# AutoPBT.net
KiCad netlist of a schematic drawn in EAGLE
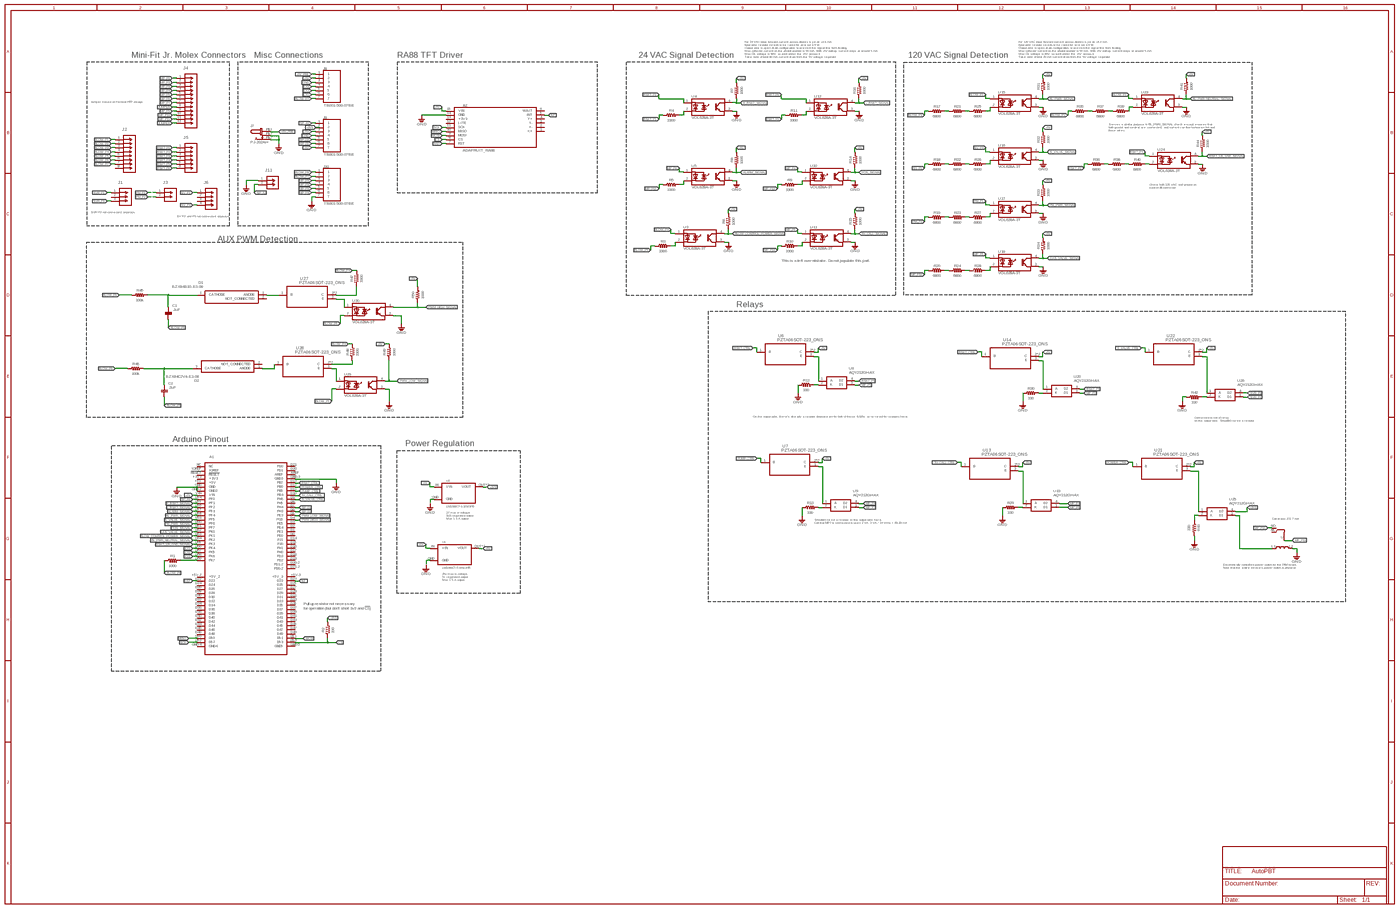
[diagram p0: schematic, sheet 1, overview]
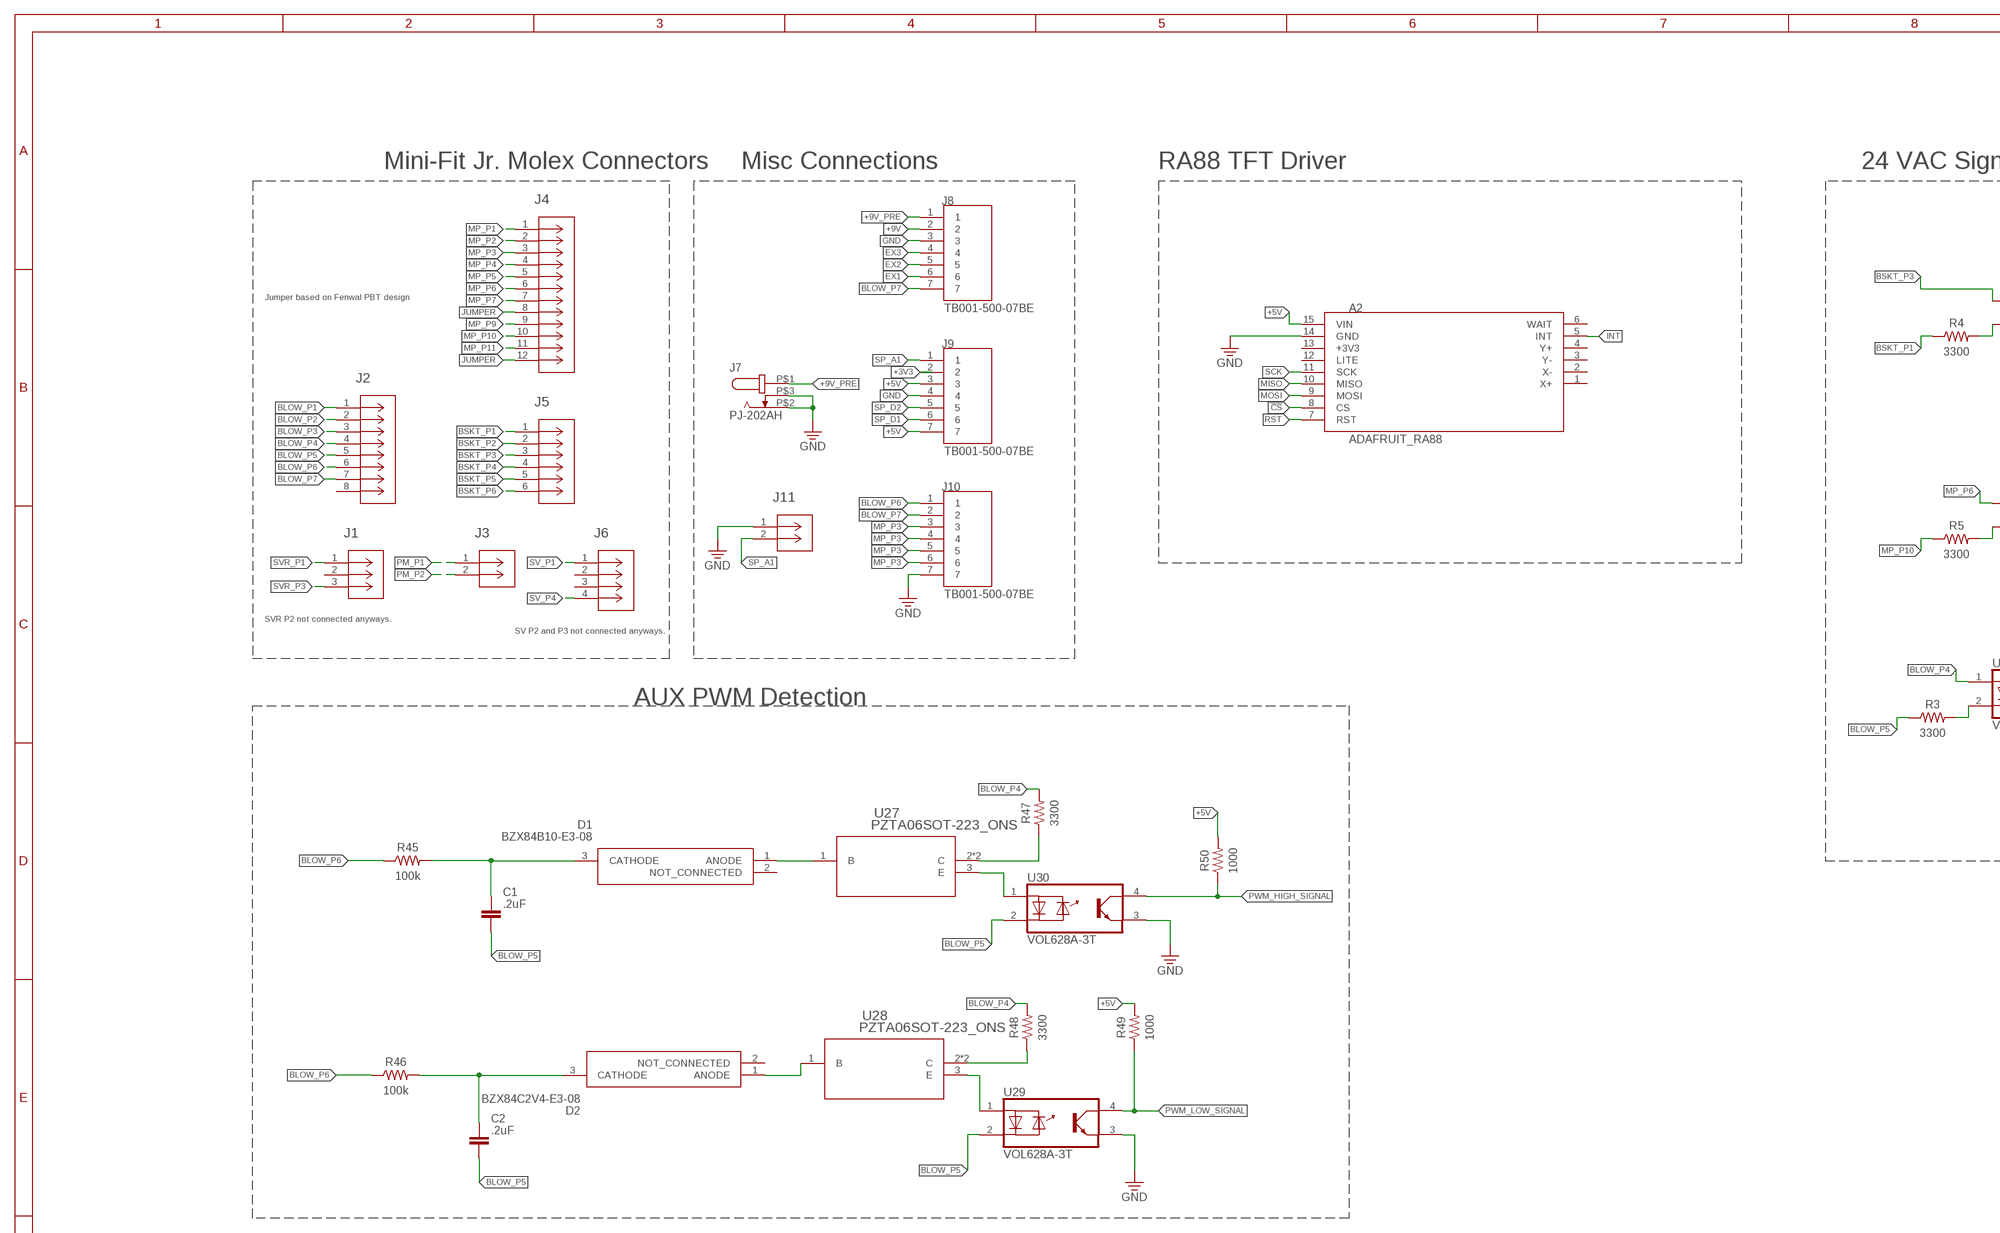
[diagram p1: schematic, sheet 1, part 1 of 4]
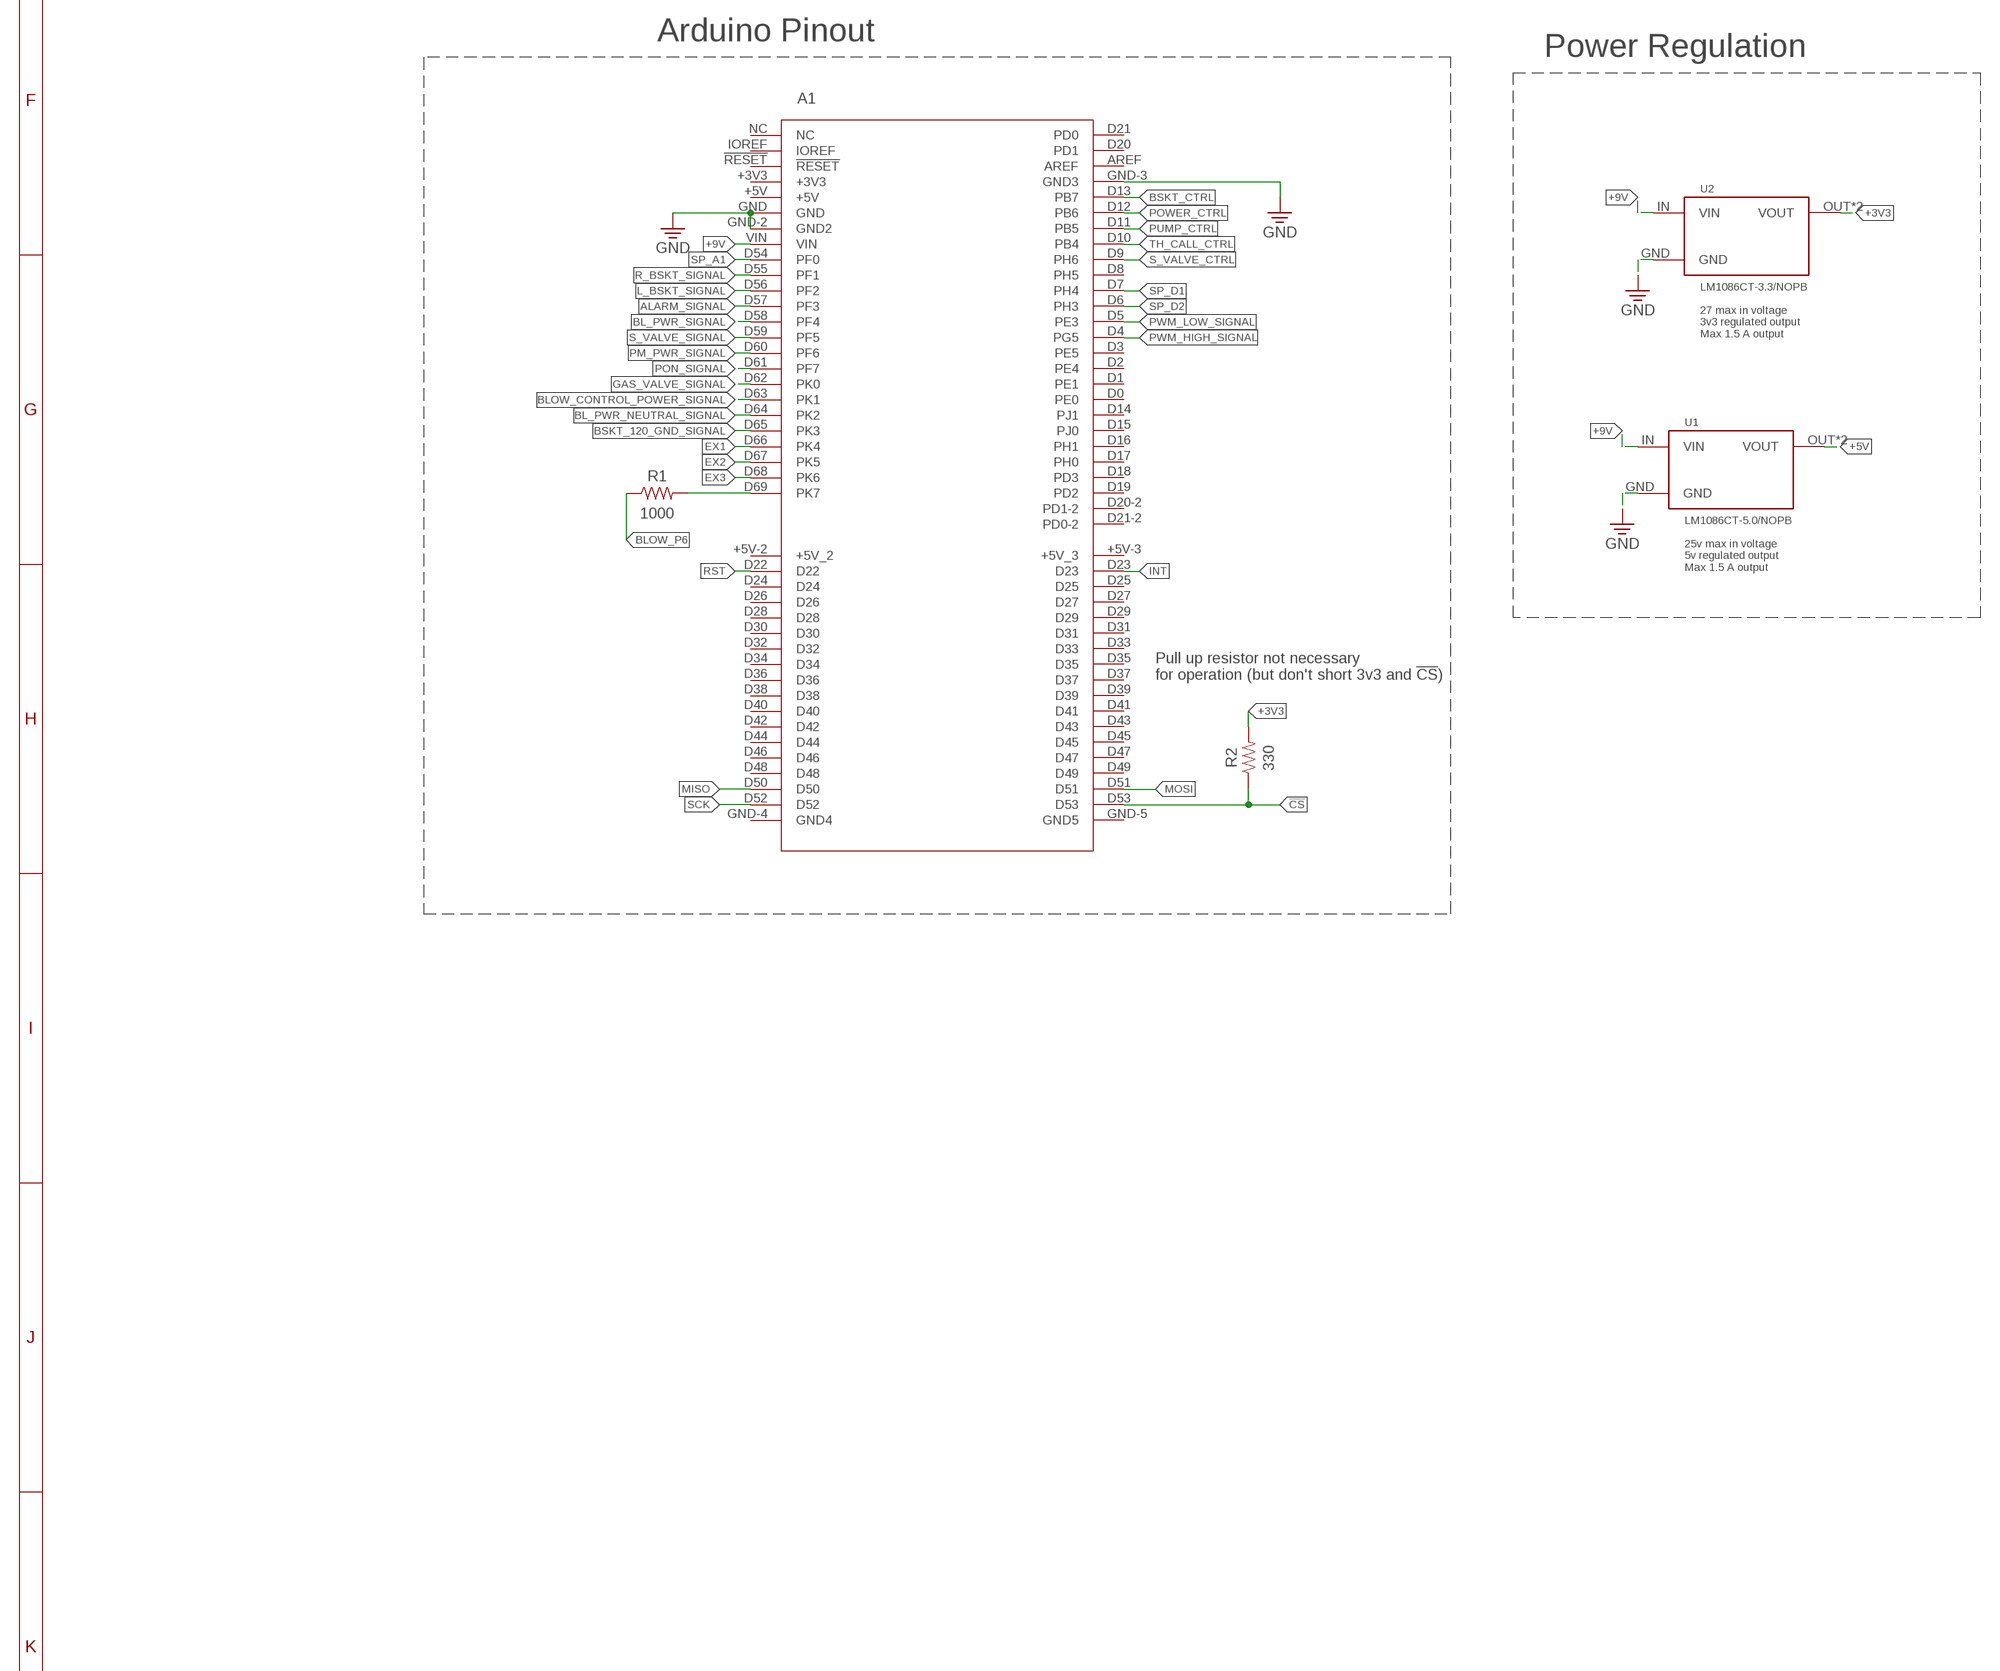
[diagram p2: schematic, sheet 1, part 2 of 4]
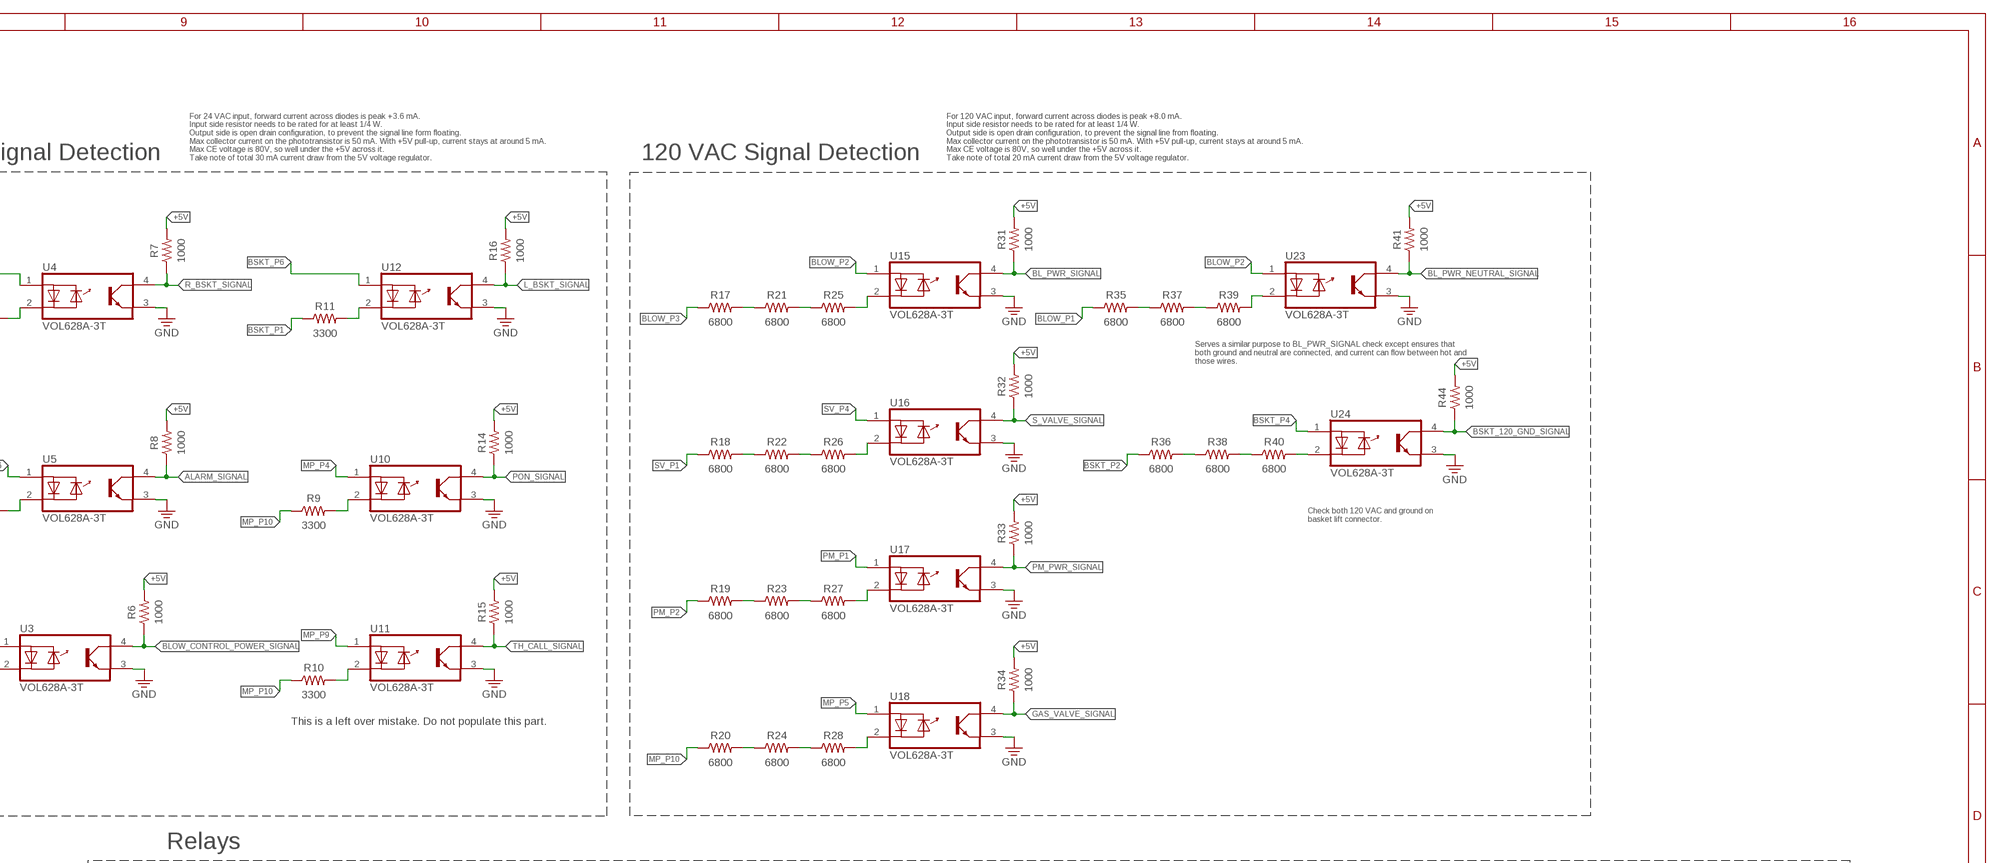
[diagram p3: schematic, sheet 1, part 3 of 4]
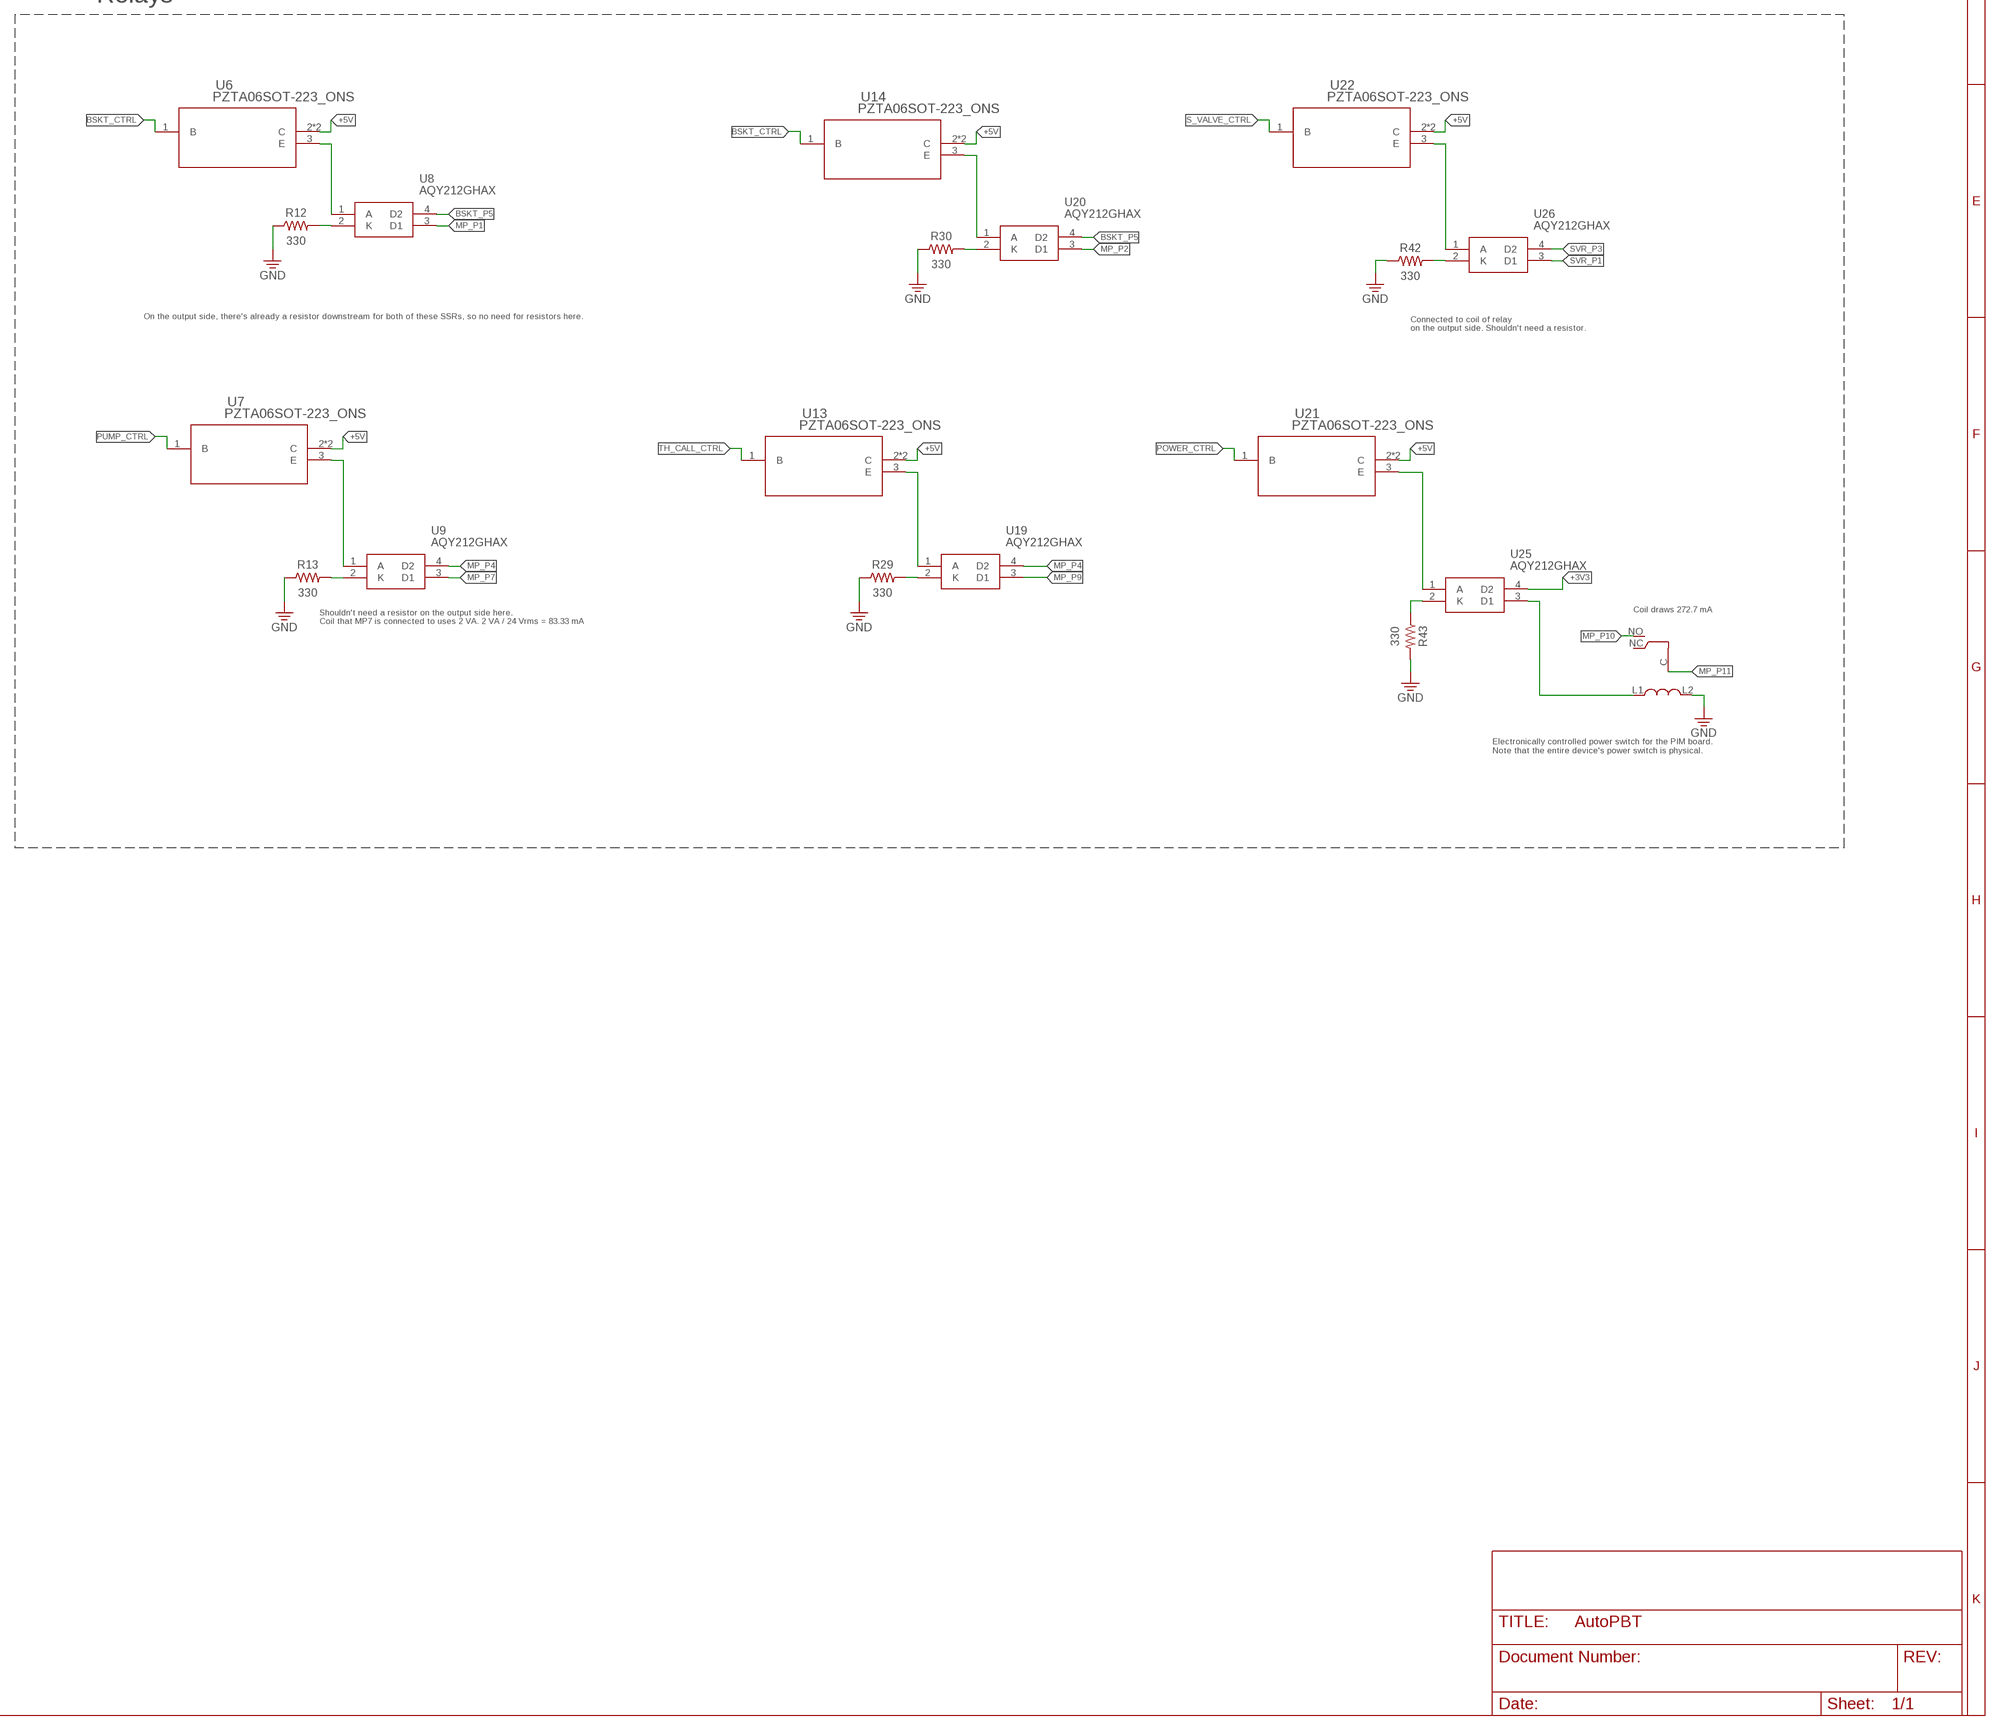
[diagram p4: schematic, sheet 1, part 4 of 4]

(export (version "E")
  (design (tool "Eeschema 10.0.6"))
  (components
    (comp (ref "A1")
      (value "ARDUINO2560ARDUINO2560ACTUAL")
      (footprint "eagle-import:ARDUINO2560PINS")
      (libsource (lib "eagle-import") (part "ARDUINO2560ARDUINO2560ACTUAL"))
    )
    (comp (ref "A2")
      (value "ADAFRUIT_RA88")
      (footprint "eagle-import:RA88")
      (libsource (lib "eagle-import") (part "ADAFRUIT_RA88"))
    )
    (comp (ref "C1")
      (value ".2uF")
      (footprint "eagle-import:CAPC3216X135")
      (libsource (lib "eagle-import") (part "CCHIP-1206(3216-METRIC)_"))
    )
    (comp (ref "C2")
      (value ".2uF")
      (footprint "eagle-import:CAPC3216X135")
      (libsource (lib "eagle-import") (part "CCHIP-1206(3216-METRIC)_"))
    )
    (comp (ref "D1")
      (value "BZX84B10-E3-08")
      (footprint "eagle-import:SOT95P248X115-3N")
      (libsource (lib "eagle-import") (part "BZX84B10-E3-08"))
    )
    (comp (ref "D2")
      (value "BZX84C2V4-E3-08")
      (footprint "eagle-import:SOT95P248X115-3N")
      (fields (field (name "MOUSER_PART_NUMBER") "78-BZX84C2V4-E3-08"))
      (libsource (lib "eagle-import") (part "BZX84C2V4-E3-08"))
    )
    (comp (ref "J1")
      (value "39301039CON_39301039")
      (footprint "eagle-import:CON_39301039")
      (fields
        (field (name "MANUFACTURER_PART_NUMBER") "39301039")
        (field (name "COPYRIGHT") "Copyright (C) 2022 Ultra Librarian. All rights reserved.")
      )
      (libsource (lib "eagle-import") (part "39301039CON_39301039"))
    )
    (comp (ref "J2")
      (value "39281083CON_39281083")
      (footprint "eagle-import:CON_39281083")
      (fields
        (field (name "MANUFACTURER_PART_NUMBER") "39281083")
        (field (name "COPYRIGHT") "Copyright (C) 2022 Ultra Librarian. All rights reserved.")
      )
      (libsource (lib "eagle-import") (part "39281083CON_39281083"))
    )
    (comp (ref "J3")
      (value "39281023CON_39281023")
      (footprint "eagle-import:CON_39281023")
      (fields
        (field (name "MANUFACTURER_PART_NUMBER") "39281023")
        (field (name "COPYRIGHT") "Copyright (C) 2022 Ultra Librarian. All rights reserved.")
      )
      (libsource (lib "eagle-import") (part "39281023CON_39281023"))
    )
    (comp (ref "J4")
      (value "39281123CON_39281123")
      (footprint "eagle-import:CON_39281123")
      (fields
        (field (name "MANUFACTURER_PART_NUMBER") "39281123")
        (field (name "COPYRIGHT") "Copyright (C) 2022 Ultra Librarian. All rights reserved.")
      )
      (libsource (lib "eagle-import") (part "39281123CON_39281123"))
    )
    (comp (ref "J5")
      (value "39281063CON_39281063")
      (footprint "eagle-import:CON_39281063")
      (fields
        (field (name "MANUFACTURER_PART_NUMBER") "39281063")
        (field (name "COPYRIGHT") "Copyright (C) 2022 Ultra Librarian. All rights reserved.")
      )
      (libsource (lib "eagle-import") (part "39281063CON_39281063"))
    )
    (comp (ref "J6")
      (value "39299046CON_39299046")
      (footprint "eagle-import:CON_39299046")
      (fields
        (field (name "MANUFACTURER_PART_NUMBER") "39299046")
        (field (name "COPYRIGHT") "Copyright (C) 2022 Ultra Librarian. All rights reserved.")
      )
      (libsource (lib "eagle-import") (part "39299046CON_39299046"))
    )
    (comp (ref "J7")
      (value "PJ-202AH")
      (footprint "eagle-import:CUI_PJ-202AH")
      (fields (field (name "MANUFACTURER") "CUI INC"))
      (libsource (lib "eagle-import") (part "PJ-202AH"))
    )
    (comp (ref "J8")
      (value "TB001-500-07BE")
      (footprint "eagle-import:CUI_TB001-500-07BE")
      (fields (field (name "MANUFACTURER") "CUI"))
      (libsource (lib "eagle-import") (part "TB001-500-07BE"))
    )
    (comp (ref "J9")
      (value "TB001-500-07BE")
      (footprint "eagle-import:CUI_TB001-500-07BE")
      (fields (field (name "MANUFACTURER") "CUI"))
      (libsource (lib "eagle-import") (part "TB001-500-07BE"))
    )
    (comp (ref "J10")
      (value "TB001-500-07BE")
      (footprint "eagle-import:CUI_TB001-500-07BE")
      (fields (field (name "MANUFACTURER") "CUI"))
      (libsource (lib "eagle-import") (part "TB001-500-07BE"))
    )
    (comp (ref "J11")
      (value "430450212CON_430450212_MOL")
      (footprint "eagle-import:CON_430450212_MOL")
      (fields
        (field (name "MANUFACTURER_PART_NUMBER") "430450212")
        (field (name "COPYRIGHT") "Copyright (C) 2022 Ultra Librarian. All rights reserved.")
      )
      (libsource (lib "eagle-import") (part "430450212CON_430450212_MOL"))
    )
    (comp (ref "K1")
      (value "J107F1CS203VDC.80")
      (footprint "eagle-import:J107F1CS203VDC.80")
      (libsource (lib "eagle-import") (part "J107F1CS203VDC.80"))
    )
    (comp (ref "R1")
      (value "1000")
      (footprint "eagle-import:RESC1608X60")
      (libsource (lib "eagle-import") (part "R-USCHIP-0603(1608-METRIC)_"))
    )
    (comp (ref "R2")
      (value "330")
      (footprint "eagle-import:RESC1608X60")
      (libsource (lib "eagle-import") (part "R-USCHIP-0603(1608-METRIC)_"))
    )
    (comp (ref "R3")
      (value "3300")
      (footprint "eagle-import:RESC1608X60")
      (libsource (lib "eagle-import") (part "R-USCHIP-0603(1608-METRIC)_"))
    )
    (comp (ref "R4")
      (value "3300")
      (footprint "eagle-import:RESC1608X60")
      (libsource (lib "eagle-import") (part "R-USCHIP-0603(1608-METRIC)_"))
    )
    (comp (ref "R5")
      (value "3300")
      (footprint "eagle-import:RESC1608X60")
      (libsource (lib "eagle-import") (part "R-USCHIP-0603(1608-METRIC)_"))
    )
    (comp (ref "R6")
      (value "1000")
      (footprint "eagle-import:RESC1608X60")
      (libsource (lib "eagle-import") (part "R-USCHIP-0603(1608-METRIC)_"))
    )
    (comp (ref "R7")
      (value "1000")
      (footprint "eagle-import:RESC1608X60")
      (libsource (lib "eagle-import") (part "R-USCHIP-0603(1608-METRIC)_"))
    )
    (comp (ref "R8")
      (value "1000")
      (footprint "eagle-import:RESC1608X60")
      (libsource (lib "eagle-import") (part "R-USCHIP-0603(1608-METRIC)_"))
    )
    (comp (ref "R9")
      (value "3300")
      (footprint "eagle-import:RESC1608X60")
      (libsource (lib "eagle-import") (part "R-USCHIP-0603(1608-METRIC)_"))
    )
    (comp (ref "R10")
      (value "3300")
      (footprint "eagle-import:RESC1608X60")
      (libsource (lib "eagle-import") (part "R-USCHIP-0603(1608-METRIC)_"))
    )
    (comp (ref "R11")
      (value "3300")
      (footprint "eagle-import:RESC1608X60")
      (libsource (lib "eagle-import") (part "R-USCHIP-0603(1608-METRIC)_"))
    )
    (comp (ref "R12")
      (value "330")
      (footprint "eagle-import:RESC1608X60")
      (libsource (lib "eagle-import") (part "R-USCHIP-0603(1608-METRIC)_"))
    )
    (comp (ref "R13")
      (value "330")
      (footprint "eagle-import:RESC1608X60")
      (libsource (lib "eagle-import") (part "R-USCHIP-0603(1608-METRIC)_"))
    )
    (comp (ref "R14")
      (value "1000")
      (footprint "eagle-import:RESC1608X60")
      (libsource (lib "eagle-import") (part "R-USCHIP-0603(1608-METRIC)_"))
    )
    (comp (ref "R15")
      (value "1000")
      (footprint "eagle-import:RESC1608X60")
      (libsource (lib "eagle-import") (part "R-USCHIP-0603(1608-METRIC)_"))
    )
    (comp (ref "R16")
      (value "1000")
      (footprint "eagle-import:RESC1608X60")
      (libsource (lib "eagle-import") (part "R-USCHIP-0603(1608-METRIC)_"))
    )
    (comp (ref "R17")
      (value "6800")
      (footprint "eagle-import:RESC1608X60")
      (libsource (lib "eagle-import") (part "R-USCHIP-0603(1608-METRIC)_"))
    )
    (comp (ref "R18")
      (value "6800")
      (footprint "eagle-import:RESC1608X60")
      (libsource (lib "eagle-import") (part "R-USCHIP-0603(1608-METRIC)_"))
    )
    (comp (ref "R19")
      (value "6800")
      (footprint "eagle-import:RESC1608X60")
      (libsource (lib "eagle-import") (part "R-USCHIP-0603(1608-METRIC)_"))
    )
    (comp (ref "R20")
      (value "6800")
      (footprint "eagle-import:RESC1608X60")
      (libsource (lib "eagle-import") (part "R-USCHIP-0603(1608-METRIC)_"))
    )
    (comp (ref "R21")
      (value "6800")
      (footprint "eagle-import:RESC1608X60")
      (libsource (lib "eagle-import") (part "R-USCHIP-0603(1608-METRIC)_"))
    )
    (comp (ref "R22")
      (value "6800")
      (footprint "eagle-import:RESC1608X60")
      (libsource (lib "eagle-import") (part "R-USCHIP-0603(1608-METRIC)_"))
    )
    (comp (ref "R23")
      (value "6800")
      (footprint "eagle-import:RESC1608X60")
      (libsource (lib "eagle-import") (part "R-USCHIP-0603(1608-METRIC)_"))
    )
    (comp (ref "R24")
      (value "6800")
      (footprint "eagle-import:RESC1608X60")
      (libsource (lib "eagle-import") (part "R-USCHIP-0603(1608-METRIC)_"))
    )
    (comp (ref "R25")
      (value "6800")
      (footprint "eagle-import:RESC1608X60")
      (libsource (lib "eagle-import") (part "R-USCHIP-0603(1608-METRIC)_"))
    )
    (comp (ref "R26")
      (value "6800")
      (footprint "eagle-import:RESC1608X60")
      (libsource (lib "eagle-import") (part "R-USCHIP-0603(1608-METRIC)_"))
    )
    (comp (ref "R27")
      (value "6800")
      (footprint "eagle-import:RESC1608X60")
      (libsource (lib "eagle-import") (part "R-USCHIP-0603(1608-METRIC)_"))
    )
    (comp (ref "R28")
      (value "6800")
      (footprint "eagle-import:RESC1608X60")
      (libsource (lib "eagle-import") (part "R-USCHIP-0603(1608-METRIC)_"))
    )
    (comp (ref "R29")
      (value "330")
      (footprint "eagle-import:RESC1608X60")
      (libsource (lib "eagle-import") (part "R-USCHIP-0603(1608-METRIC)_"))
    )
    (comp (ref "R30")
      (value "330")
      (footprint "eagle-import:RESC1608X60")
      (libsource (lib "eagle-import") (part "R-USCHIP-0603(1608-METRIC)_"))
    )
    (comp (ref "R31")
      (value "1000")
      (footprint "eagle-import:RESC1608X60")
      (libsource (lib "eagle-import") (part "R-USCHIP-0603(1608-METRIC)_"))
    )
    (comp (ref "R32")
      (value "1000")
      (footprint "eagle-import:RESC1608X60")
      (libsource (lib "eagle-import") (part "R-USCHIP-0603(1608-METRIC)_"))
    )
    (comp (ref "R33")
      (value "1000")
      (footprint "eagle-import:RESC1608X60")
      (libsource (lib "eagle-import") (part "R-USCHIP-0603(1608-METRIC)_"))
    )
    (comp (ref "R34")
      (value "1000")
      (footprint "eagle-import:RESC1608X60")
      (libsource (lib "eagle-import") (part "R-USCHIP-0603(1608-METRIC)_"))
    )
    (comp (ref "R35")
      (value "6800")
      (footprint "eagle-import:RESC1608X60")
      (libsource (lib "eagle-import") (part "R-USCHIP-0603(1608-METRIC)_"))
    )
    (comp (ref "R36")
      (value "6800")
      (footprint "eagle-import:RESC1608X60")
      (libsource (lib "eagle-import") (part "R-USCHIP-0603(1608-METRIC)_"))
    )
    (comp (ref "R37")
      (value "6800")
      (footprint "eagle-import:RESC1608X60")
      (libsource (lib "eagle-import") (part "R-USCHIP-0603(1608-METRIC)_"))
    )
    (comp (ref "R38")
      (value "6800")
      (footprint "eagle-import:RESC1608X60")
      (libsource (lib "eagle-import") (part "R-USCHIP-0603(1608-METRIC)_"))
    )
    (comp (ref "R39")
      (value "6800")
      (footprint "eagle-import:RESC1608X60")
      (libsource (lib "eagle-import") (part "R-USCHIP-0603(1608-METRIC)_"))
    )
    (comp (ref "R40")
      (value "6800")
      (footprint "eagle-import:RESC1608X60")
      (libsource (lib "eagle-import") (part "R-USCHIP-0603(1608-METRIC)_"))
    )
    (comp (ref "R41")
      (value "1000")
      (footprint "eagle-import:RESC1608X60")
      (libsource (lib "eagle-import") (part "R-USCHIP-0603(1608-METRIC)_"))
    )
    (comp (ref "R42")
      (value "330")
      (footprint "eagle-import:RESC1608X60")
      (libsource (lib "eagle-import") (part "R-USCHIP-0603(1608-METRIC)_"))
    )
    (comp (ref "R43")
      (value "330")
      (footprint "eagle-import:RESC1608X60")
      (libsource (lib "eagle-import") (part "R-USCHIP-0603(1608-METRIC)_"))
    )
    (comp (ref "R44")
      (value "1000")
      (footprint "eagle-import:RESC1608X60")
      (libsource (lib "eagle-import") (part "R-USCHIP-0603(1608-METRIC)_"))
    )
    (comp (ref "R45")
      (value "100k")
      (footprint "eagle-import:RESC6332X71")
      (libsource (lib "eagle-import") (part "R-USCHIP-2512(6332-METRIC)_"))
    )
    (comp (ref "R46")
      (value "100k")
      (footprint "eagle-import:RESC6332X71")
      (libsource (lib "eagle-import") (part "R-USCHIP-2512(6332-METRIC)_"))
    )
    (comp (ref "R47")
      (value "3300")
      (footprint "eagle-import:RESC1608X60")
      (libsource (lib "eagle-import") (part "R-USCHIP-0603(1608-METRIC)_"))
    )
    (comp (ref "R48")
      (value "3300")
      (footprint "eagle-import:RESC1608X60")
      (libsource (lib "eagle-import") (part "R-USCHIP-0603(1608-METRIC)_"))
    )
    (comp (ref "R49")
      (value "1000")
      (footprint "eagle-import:RESC1608X60")
      (libsource (lib "eagle-import") (part "R-USCHIP-0603(1608-METRIC)_"))
    )
    (comp (ref "R50")
      (value "1000")
      (footprint "eagle-import:RESC1608X60")
      (libsource (lib "eagle-import") (part "R-USCHIP-0603(1608-METRIC)_"))
    )
    (comp (ref "U1")
      (value "LM1086CT-5.0/NOPB")
      (footprint "eagle-import:LM1086CT-3.3_NOPB")
      (libsource (lib "eagle-import") (part "LM1086CT-5.0/NOPB"))
    )
    (comp (ref "U2")
      (value "LM1086CT-3.3/NOPB")
      (footprint "eagle-import:LM1086CT-3.3_NOPB")
      (libsource (lib "eagle-import") (part "LM1086CT-3.3/NOPB"))
    )
    (comp (ref "U3")
      (value "VOL628A-3T")
      (footprint "eagle-import:SOIC254P1020X230-4N")
      (fields (field (name "MANUFACTURER") "VISHAY"))
      (libsource (lib "eagle-import") (part "VOL628A-3T"))
    )
    (comp (ref "U4")
      (value "VOL628A-3T")
      (footprint "eagle-import:SOIC254P1020X230-4N")
      (fields (field (name "MANUFACTURER") "VISHAY"))
      (libsource (lib "eagle-import") (part "VOL628A-3T"))
    )
    (comp (ref "U5")
      (value "VOL628A-3T")
      (footprint "eagle-import:SOIC254P1020X230-4N")
      (fields (field (name "MANUFACTURER") "VISHAY"))
      (libsource (lib "eagle-import") (part "VOL628A-3T"))
    )
    (comp (ref "U6")
      (value "PZTA06SOT-223_ONS")
      (footprint "eagle-import:SOT-223_ONS")
      (fields
        (field (name "MANUFACTURER_PART_NUMBER") "PZTA06")
        (field (name "COPYRIGHT") "Copyright (C) 2022 Ultra Librarian. All rights reserved.")
      )
      (libsource (lib "eagle-import") (part "PZTA06SOT-223_ONS"))
    )
    (comp (ref "U7")
      (value "PZTA06SOT-223_ONS")
      (footprint "eagle-import:SOT-223_ONS")
      (fields
        (field (name "MANUFACTURER_PART_NUMBER") "PZTA06")
        (field (name "COPYRIGHT") "Copyright (C) 2022 Ultra Librarian. All rights reserved.")
      )
      (libsource (lib "eagle-import") (part "PZTA06SOT-223_ONS"))
    )
    (comp (ref "U8")
      (value "AQY212GHAX")
      (footprint "eagle-import:SOP254P962X315-4N")
      (fields (field (name "MOUSER_PART_NUMBER") "667-AQY212GHAX"))
      (libsource (lib "eagle-import") (part "AQY212GHAX"))
    )
    (comp (ref "U9")
      (value "AQY212GHAX")
      (footprint "eagle-import:SOP254P962X315-4N")
      (fields (field (name "MOUSER_PART_NUMBER") "667-AQY212GHAX"))
      (libsource (lib "eagle-import") (part "AQY212GHAX"))
    )
    (comp (ref "U10")
      (value "VOL628A-3T")
      (footprint "eagle-import:SOIC254P1020X230-4N")
      (fields (field (name "MANUFACTURER") "VISHAY"))
      (libsource (lib "eagle-import") (part "VOL628A-3T"))
    )
    (comp (ref "U11")
      (value "VOL628A-3T")
      (footprint "eagle-import:SOIC254P1020X230-4N")
      (fields (field (name "MANUFACTURER") "VISHAY"))
      (libsource (lib "eagle-import") (part "VOL628A-3T"))
    )
    (comp (ref "U12")
      (value "VOL628A-3T")
      (footprint "eagle-import:SOIC254P1020X230-4N")
      (fields (field (name "MANUFACTURER") "VISHAY"))
      (libsource (lib "eagle-import") (part "VOL628A-3T"))
    )
    (comp (ref "U13")
      (value "PZTA06SOT-223_ONS")
      (footprint "eagle-import:SOT-223_ONS")
      (fields
        (field (name "MANUFACTURER_PART_NUMBER") "PZTA06")
        (field (name "COPYRIGHT") "Copyright (C) 2022 Ultra Librarian. All rights reserved.")
      )
      (libsource (lib "eagle-import") (part "PZTA06SOT-223_ONS"))
    )
    (comp (ref "U14")
      (value "PZTA06SOT-223_ONS")
      (footprint "eagle-import:SOT-223_ONS")
      (fields
        (field (name "MANUFACTURER_PART_NUMBER") "PZTA06")
        (field (name "COPYRIGHT") "Copyright (C) 2022 Ultra Librarian. All rights reserved.")
      )
      (libsource (lib "eagle-import") (part "PZTA06SOT-223_ONS"))
    )
    (comp (ref "U15")
      (value "VOL628A-3T")
      (footprint "eagle-import:SOIC254P1020X230-4N")
      (fields (field (name "MANUFACTURER") "VISHAY"))
      (libsource (lib "eagle-import") (part "VOL628A-3T"))
    )
    (comp (ref "U16")
      (value "VOL628A-3T")
      (footprint "eagle-import:SOIC254P1020X230-4N")
      (fields (field (name "MANUFACTURER") "VISHAY"))
      (libsource (lib "eagle-import") (part "VOL628A-3T"))
    )
    (comp (ref "U17")
      (value "VOL628A-3T")
      (footprint "eagle-import:SOIC254P1020X230-4N")
      (fields (field (name "MANUFACTURER") "VISHAY"))
      (libsource (lib "eagle-import") (part "VOL628A-3T"))
    )
    (comp (ref "U18")
      (value "VOL628A-3T")
      (footprint "eagle-import:SOIC254P1020X230-4N")
      (fields (field (name "MANUFACTURER") "VISHAY"))
      (libsource (lib "eagle-import") (part "VOL628A-3T"))
    )
    (comp (ref "U19")
      (value "AQY212GHAX")
      (footprint "eagle-import:SOP254P962X315-4N")
      (fields (field (name "MOUSER_PART_NUMBER") "667-AQY212GHAX"))
      (libsource (lib "eagle-import") (part "AQY212GHAX"))
    )
    (comp (ref "U20")
      (value "AQY212GHAX")
      (footprint "eagle-import:SOP254P962X315-4N")
      (fields (field (name "MOUSER_PART_NUMBER") "667-AQY212GHAX"))
      (libsource (lib "eagle-import") (part "AQY212GHAX"))
    )
    (comp (ref "U21")
      (value "PZTA06SOT-223_ONS")
      (footprint "eagle-import:SOT-223_ONS")
      (fields
        (field (name "MANUFACTURER_PART_NUMBER") "PZTA06")
        (field (name "COPYRIGHT") "Copyright (C) 2022 Ultra Librarian. All rights reserved.")
      )
      (libsource (lib "eagle-import") (part "PZTA06SOT-223_ONS"))
    )
    (comp (ref "U22")
      (value "PZTA06SOT-223_ONS")
      (footprint "eagle-import:SOT-223_ONS")
      (fields
        (field (name "MANUFACTURER_PART_NUMBER") "PZTA06")
        (field (name "COPYRIGHT") "Copyright (C) 2022 Ultra Librarian. All rights reserved.")
      )
      (libsource (lib "eagle-import") (part "PZTA06SOT-223_ONS"))
    )
    (comp (ref "U23")
      (value "VOL628A-3T")
      (footprint "eagle-import:SOIC254P1020X230-4N")
      (fields (field (name "MANUFACTURER") "VISHAY"))
      (libsource (lib "eagle-import") (part "VOL628A-3T"))
    )
    (comp (ref "U24")
      (value "VOL628A-3T")
      (footprint "eagle-import:SOIC254P1020X230-4N")
      (fields (field (name "MANUFACTURER") "VISHAY"))
      (libsource (lib "eagle-import") (part "VOL628A-3T"))
    )
    (comp (ref "U25")
      (value "AQY212GHAX")
      (footprint "eagle-import:SOP254P962X315-4N")
      (fields (field (name "MOUSER_PART_NUMBER") "667-AQY212GHAX"))
      (libsource (lib "eagle-import") (part "AQY212GHAX"))
    )
    (comp (ref "U26")
      (value "AQY212GHAX")
      (footprint "eagle-import:SOP254P962X315-4N")
      (fields (field (name "MOUSER_PART_NUMBER") "667-AQY212GHAX"))
      (libsource (lib "eagle-import") (part "AQY212GHAX"))
    )
    (comp (ref "U27")
      (value "PZTA06SOT-223_ONS")
      (footprint "eagle-import:SOT-223_ONS")
      (fields
        (field (name "MANUFACTURER_PART_NUMBER") "PZTA06")
        (field (name "COPYRIGHT") "Copyright (C) 2022 Ultra Librarian. All rights reserved.")
      )
      (libsource (lib "eagle-import") (part "PZTA06SOT-223_ONS"))
    )
    (comp (ref "U28")
      (value "PZTA06SOT-223_ONS")
      (footprint "eagle-import:SOT-223_ONS")
      (fields
        (field (name "MANUFACTURER_PART_NUMBER") "PZTA06")
        (field (name "COPYRIGHT") "Copyright (C) 2022 Ultra Librarian. All rights reserved.")
      )
      (libsource (lib "eagle-import") (part "PZTA06SOT-223_ONS"))
    )
    (comp (ref "U29")
      (value "VOL628A-3T")
      (footprint "eagle-import:SOIC254P1020X230-4N")
      (fields (field (name "MANUFACTURER") "VISHAY"))
      (libsource (lib "eagle-import") (part "VOL628A-3T"))
    )
    (comp (ref "U30")
      (value "VOL628A-3T")
      (footprint "eagle-import:SOIC254P1020X230-4N")
      (fields (field (name "MANUFACTURER") "VISHAY"))
      (libsource (lib "eagle-import") (part "VOL628A-3T"))
    )
  )
  (nets
    (net (code "1") (name "+3V3") (class "Default")
      (node (ref "J9") (pin "2") (pinfunction "2_2") (pintype "passive"))
      (node (ref "R2") (pin "2") (pinfunction "2_2") (pintype "passive"))
      (node (ref "U2") (pin "OUT") (pinfunction "VOUT_OUT") (pintype "bidirectional"))
      (node (ref "U2") (pin "OUT2") (pinfunction "VOUT_OUT2") (pintype "bidirectional"))
      (node (ref "U25") (pin "4") (pinfunction "D2_4") (pintype "bidirectional"))
    )
    (net (code "2") (name "+5V") (class "Default")
      (node (ref "A2") (pin "15") (pinfunction "VIN_15") (pintype "bidirectional"))
      (node (ref "J9") (pin "3") (pinfunction "3_3") (pintype "passive"))
      (node (ref "J9") (pin "7") (pinfunction "7_7") (pintype "passive"))
      (node (ref "R14") (pin "2") (pinfunction "2_2") (pintype "passive"))
      (node (ref "R15") (pin "2") (pinfunction "2_2") (pintype "passive"))
      (node (ref "R16") (pin "2") (pinfunction "2_2") (pintype "passive"))
      (node (ref "R31") (pin "2") (pinfunction "2_2") (pintype "passive"))
      (node (ref "R32") (pin "2") (pinfunction "2_2") (pintype "passive"))
      (node (ref "R33") (pin "2") (pinfunction "2_2") (pintype "passive"))
      (node (ref "R34") (pin "2") (pinfunction "2_2") (pintype "passive"))
      (node (ref "R41") (pin "2") (pinfunction "2_2") (pintype "passive"))
      (node (ref "R44") (pin "2") (pinfunction "2_2") (pintype "passive"))
      (node (ref "R49") (pin "2") (pinfunction "2_2") (pintype "passive"))
      (node (ref "R50") (pin "2") (pinfunction "2_2") (pintype "passive"))
      (node (ref "R6") (pin "2") (pinfunction "2_2") (pintype "passive"))
      (node (ref "R7") (pin "2") (pinfunction "2_2") (pintype "passive"))
      (node (ref "R8") (pin "2") (pinfunction "2_2") (pintype "passive"))
      (node (ref "U1") (pin "OUT") (pinfunction "VOUT_OUT") (pintype "bidirectional"))
      (node (ref "U1") (pin "OUT2") (pinfunction "VOUT_OUT2") (pintype "bidirectional"))
      (node (ref "U13") (pin "2") (pinfunction "C_2") (pintype "passive"))
      (node (ref "U13") (pin "4") (pinfunction "C_4") (pintype "passive"))
      (node (ref "U14") (pin "2") (pinfunction "C_2") (pintype "passive"))
      (node (ref "U14") (pin "4") (pinfunction "C_4") (pintype "passive"))
      (node (ref "U21") (pin "2") (pinfunction "C_2") (pintype "passive"))
      (node (ref "U21") (pin "4") (pinfunction "C_4") (pintype "passive"))
      (node (ref "U22") (pin "2") (pinfunction "C_2") (pintype "passive"))
      (node (ref "U22") (pin "4") (pinfunction "C_4") (pintype "passive"))
      (node (ref "U6") (pin "2") (pinfunction "C_2") (pintype "passive"))
      (node (ref "U6") (pin "4") (pinfunction "C_4") (pintype "passive"))
      (node (ref "U7") (pin "2") (pinfunction "C_2") (pintype "passive"))
      (node (ref "U7") (pin "4") (pinfunction "C_4") (pintype "passive"))
    )
    (net (code "3") (name "+9V") (class "Default")
      (node (ref "A1") (pin "VIN") (pinfunction "VIN_VIN") (pintype "bidirectional"))
      (node (ref "J8") (pin "2") (pinfunction "2_2") (pintype "passive"))
      (node (ref "U1") (pin "IN") (pinfunction "VIN_IN") (pintype "bidirectional"))
      (node (ref "U2") (pin "IN") (pinfunction "VIN_IN") (pintype "bidirectional"))
    )
    (net (code "4") (name "+9V_PRE") (class "Default")
      (node (ref "J7") (pin "P$1") (pinfunction "1_P$1") (pintype "passive"))
      (node (ref "J8") (pin "1") (pinfunction "1_1") (pintype "passive"))
    )
    (net (code "5") (name "/~{CS}") (class "Default")
      (node (ref "A1") (pin "D53") (pinfunction "D53_D53") (pintype "bidirectional"))
      (node (ref "A2") (pin "8") (pinfunction "CS_8") (pintype "bidirectional"))
      (node (ref "R2") (pin "1") (pinfunction "1_1") (pintype "passive"))
    )
    (net (code "6") (name "ALARM_SIGNAL") (class "Default")
      (node (ref "A1") (pin "D57") (pinfunction "PF3_D57") (pintype "bidirectional"))
      (node (ref "R8") (pin "1") (pinfunction "1_1") (pintype "passive"))
      (node (ref "U5") (pin "4") (pinfunction "CO_4") (pintype "passive"))
    )
    (net (code "7") (name "BLOW_CONTROL_POWER_SIGNAL") (class "Default")
      (node (ref "A1") (pin "D63") (pinfunction "PK1_D63") (pintype "bidirectional"))
      (node (ref "R6") (pin "1") (pinfunction "1_1") (pintype "passive"))
      (node (ref "U3") (pin "4") (pinfunction "CO_4") (pintype "passive"))
    )
    (net (code "8") (name "BLOW_P1") (class "Default")
      (node (ref "J2") (pin "1") (pinfunction "1_1") (pintype "passive"))
      (node (ref "R35") (pin "1") (pinfunction "1_1") (pintype "passive"))
    )
    (net (code "9") (name "BLOW_P2") (class "Default")
      (node (ref "J2") (pin "2") (pinfunction "2_2") (pintype "passive"))
      (node (ref "U15") (pin "1") (pinfunction "A/C_1") (pintype "passive"))
      (node (ref "U23") (pin "1") (pinfunction "A/C_1") (pintype "passive"))
    )
    (net (code "10") (name "BLOW_P3") (class "Default")
      (node (ref "J2") (pin "3") (pinfunction "3_3") (pintype "passive"))
      (node (ref "R17") (pin "1") (pinfunction "1_1") (pintype "passive"))
    )
    (net (code "11") (name "BLOW_P4") (class "Default")
      (node (ref "J2") (pin "4") (pinfunction "4_4") (pintype "passive"))
      (node (ref "R47") (pin "2") (pinfunction "2_2") (pintype "passive"))
      (node (ref "R48") (pin "2") (pinfunction "2_2") (pintype "passive"))
      (node (ref "U3") (pin "1") (pinfunction "A/C_1") (pintype "passive"))
    )
    (net (code "12") (name "BLOW_P5") (class "Default")
      (node (ref "C1") (pin "2") (pinfunction "2_2") (pintype "passive"))
      (node (ref "C2") (pin "2") (pinfunction "2_2") (pintype "passive"))
      (node (ref "J2") (pin "5") (pinfunction "5_5") (pintype "passive"))
      (node (ref "R3") (pin "1") (pinfunction "1_1") (pintype "passive"))
      (node (ref "U29") (pin "2") (pinfunction "C/A_2") (pintype "passive"))
      (node (ref "U30") (pin "2") (pinfunction "C/A_2") (pintype "passive"))
    )
    (net (code "13") (name "BLOW_P6") (class "Default")
      (node (ref "J10") (pin "1") (pinfunction "1_1") (pintype "passive"))
      (node (ref "J2") (pin "6") (pinfunction "6_6") (pintype "passive"))
      (node (ref "R1") (pin "1") (pinfunction "1_1") (pintype "passive"))
      (node (ref "R45") (pin "1") (pinfunction "1_1") (pintype "passive"))
      (node (ref "R46") (pin "1") (pinfunction "1_1") (pintype "passive"))
    )
    (net (code "14") (name "BLOW_P7") (class "Default")
      (node (ref "J10") (pin "2") (pinfunction "2_2") (pintype "passive"))
      (node (ref "J2") (pin "7") (pinfunction "7_7") (pintype "passive"))
      (node (ref "J8") (pin "7") (pinfunction "7_7") (pintype "passive"))
    )
    (net (code "15") (name "BL_PWR_NEUTRAL_SIGNAL") (class "Default")
      (node (ref "A1") (pin "D64") (pinfunction "PK2_D64") (pintype "bidirectional"))
      (node (ref "R41") (pin "1") (pinfunction "1_1") (pintype "passive"))
      (node (ref "U23") (pin "4") (pinfunction "CO_4") (pintype "passive"))
    )
    (net (code "16") (name "BL_PWR_SIGNAL") (class "Default")
      (node (ref "A1") (pin "D58") (pinfunction "PF4_D58") (pintype "bidirectional"))
      (node (ref "R31") (pin "1") (pinfunction "1_1") (pintype "passive"))
      (node (ref "U15") (pin "4") (pinfunction "CO_4") (pintype "passive"))
    )
    (net (code "17") (name "BSKT_120_GND_SIGNAL") (class "Default")
      (node (ref "A1") (pin "D65") (pinfunction "PK3_D65") (pintype "bidirectional"))
      (node (ref "R44") (pin "1") (pinfunction "1_1") (pintype "passive"))
      (node (ref "U24") (pin "4") (pinfunction "CO_4") (pintype "passive"))
    )
    (net (code "18") (name "BSKT_CTRL") (class "Default")
      (node (ref "A1") (pin "D13") (pinfunction "PB7_D13") (pintype "bidirectional"))
      (node (ref "U14") (pin "1") (pinfunction "B_1") (pintype "passive"))
      (node (ref "U6") (pin "1") (pinfunction "B_1") (pintype "passive"))
    )
    (net (code "19") (name "BSKT_P1") (class "Default")
      (node (ref "J5") (pin "1") (pinfunction "1_1") (pintype "passive"))
      (node (ref "R11") (pin "1") (pinfunction "1_1") (pintype "passive"))
      (node (ref "R4") (pin "1") (pinfunction "1_1") (pintype "passive"))
    )
    (net (code "20") (name "BSKT_P2") (class "Default")
      (node (ref "J5") (pin "2") (pinfunction "2_2") (pintype "passive"))
      (node (ref "R36") (pin "1") (pinfunction "1_1") (pintype "passive"))
    )
    (net (code "21") (name "BSKT_P3") (class "Default")
      (node (ref "J5") (pin "3") (pinfunction "3_3") (pintype "passive"))
      (node (ref "U4") (pin "1") (pinfunction "A/C_1") (pintype "passive"))
    )
    (net (code "22") (name "BSKT_P4") (class "Default")
      (node (ref "J5") (pin "4") (pinfunction "4_4") (pintype "passive"))
      (node (ref "U24") (pin "1") (pinfunction "A/C_1") (pintype "passive"))
    )
    (net (code "23") (name "BSKT_P5") (class "Default")
      (node (ref "J5") (pin "5") (pinfunction "5_5") (pintype "passive"))
      (node (ref "U20") (pin "4") (pinfunction "D2_4") (pintype "bidirectional"))
      (node (ref "U8") (pin "4") (pinfunction "D2_4") (pintype "bidirectional"))
    )
    (net (code "24") (name "BSKT_P6") (class "Default")
      (node (ref "J5") (pin "6") (pinfunction "6_6") (pintype "passive"))
      (node (ref "U12") (pin "1") (pinfunction "A/C_1") (pintype "passive"))
    )
    (net (code "25") (name "EX1") (class "Default")
      (node (ref "A1") (pin "D66") (pinfunction "PK4_D66") (pintype "bidirectional"))
      (node (ref "J8") (pin "6") (pinfunction "6_6") (pintype "passive"))
    )
    (net (code "26") (name "EX2") (class "Default")
      (node (ref "A1") (pin "D67") (pinfunction "PK5_D67") (pintype "bidirectional"))
      (node (ref "J8") (pin "5") (pinfunction "5_5") (pintype "passive"))
    )
    (net (code "27") (name "EX3") (class "Default")
      (node (ref "A1") (pin "D68") (pinfunction "PK6_D68") (pintype "bidirectional"))
      (node (ref "J8") (pin "4") (pinfunction "4_4") (pintype "passive"))
    )
    (net (code "28") (name "GAS_VALVE_SIGNAL") (class "Default")
      (node (ref "A1") (pin "D62") (pinfunction "PK0_D62") (pintype "bidirectional"))
      (node (ref "R34") (pin "1") (pinfunction "1_1") (pintype "passive"))
      (node (ref "U18") (pin "4") (pinfunction "CO_4") (pintype "passive"))
    )
    (net (code "29") (name "GND") (class "Default")
      (node (ref "A1") (pin "GND") (pinfunction "GND_GND") (pintype "bidirectional"))
      (node (ref "A1") (pin "GND-2") (pinfunction "GND2_GND-2") (pintype "bidirectional"))
      (node (ref "A1") (pin "GND-3") (pinfunction "GND3_GND-3") (pintype "bidirectional"))
      (node (ref "A2") (pin "14") (pinfunction "GND_14") (pintype "bidirectional"))
      (node (ref "J10") (pin "7") (pinfunction "7_7") (pintype "passive"))
      (node (ref "J11") (pin "1") (pinfunction "1_1") (pintype "passive"))
      (node (ref "J7") (pin "P$2") (pinfunction "2_P$2") (pintype "passive"))
      (node (ref "J7") (pin "P$3") (pinfunction "3_P$3") (pintype "passive"))
      (node (ref "J8") (pin "3") (pinfunction "3_3") (pintype "passive"))
      (node (ref "J9") (pin "4") (pinfunction "4_4") (pintype "passive"))
      (node (ref "K1") (pin "L2") (pinfunction "5_L2") (pintype "bidirectional"))
      (node (ref "R12") (pin "1") (pinfunction "1_1") (pintype "passive"))
      (node (ref "R13") (pin "1") (pinfunction "1_1") (pintype "passive"))
      (node (ref "R29") (pin "1") (pinfunction "1_1") (pintype "passive"))
      (node (ref "R30") (pin "1") (pinfunction "1_1") (pintype "passive"))
      (node (ref "R42") (pin "1") (pinfunction "1_1") (pintype "passive"))
      (node (ref "R43") (pin "2") (pinfunction "2_2") (pintype "passive"))
      (node (ref "U1") (pin "GND") (pinfunction "GND_GND") (pintype "bidirectional"))
      (node (ref "U10") (pin "3") (pinfunction "E_3") (pintype "passive"))
      (node (ref "U11") (pin "3") (pinfunction "E_3") (pintype "passive"))
      (node (ref "U12") (pin "3") (pinfunction "E_3") (pintype "passive"))
      (node (ref "U15") (pin "3") (pinfunction "E_3") (pintype "passive"))
      (node (ref "U16") (pin "3") (pinfunction "E_3") (pintype "passive"))
      (node (ref "U17") (pin "3") (pinfunction "E_3") (pintype "passive"))
      (node (ref "U18") (pin "3") (pinfunction "E_3") (pintype "passive"))
      (node (ref "U2") (pin "GND") (pinfunction "GND_GND") (pintype "bidirectional"))
      (node (ref "U23") (pin "3") (pinfunction "E_3") (pintype "passive"))
      (node (ref "U24") (pin "3") (pinfunction "E_3") (pintype "passive"))
      (node (ref "U29") (pin "3") (pinfunction "E_3") (pintype "passive"))
      (node (ref "U3") (pin "3") (pinfunction "E_3") (pintype "passive"))
      (node (ref "U30") (pin "3") (pinfunction "E_3") (pintype "passive"))
      (node (ref "U4") (pin "3") (pinfunction "E_3") (pintype "passive"))
      (node (ref "U5") (pin "3") (pinfunction "E_3") (pintype "passive"))
    )
    (net (code "30") (name "INT") (class "Default")
      (node (ref "A1") (pin "D23") (pinfunction "D23_D23") (pintype "bidirectional"))
      (node (ref "A2") (pin "5") (pinfunction "INT_5") (pintype "bidirectional"))
    )
    (net (code "31") (name "JUMPER") (class "Default")
      (node (ref "J4") (pin "12") (pinfunction "12_12") (pintype "passive"))
      (node (ref "J4") (pin "8") (pinfunction "8_8") (pintype "passive"))
    )
    (net (code "32") (name "L_BSKT_SIGNAL") (class "Default")
      (node (ref "A1") (pin "D56") (pinfunction "PF2_D56") (pintype "bidirectional"))
      (node (ref "R16") (pin "1") (pinfunction "1_1") (pintype "passive"))
      (node (ref "U12") (pin "4") (pinfunction "CO_4") (pintype "passive"))
    )
    (net (code "33") (name "MISO") (class "Default")
      (node (ref "A1") (pin "D50") (pinfunction "D50_D50") (pintype "bidirectional"))
      (node (ref "A2") (pin "10") (pinfunction "MISO_10") (pintype "bidirectional"))
    )
    (net (code "34") (name "MOSI") (class "Default")
      (node (ref "A1") (pin "D51") (pinfunction "D51_D51") (pintype "bidirectional"))
      (node (ref "A2") (pin "9") (pinfunction "MOSI_9") (pintype "bidirectional"))
    )
    (net (code "35") (name "MP_P1") (class "Default")
      (node (ref "J4") (pin "1") (pinfunction "1_1") (pintype "passive"))
      (node (ref "U8") (pin "3") (pinfunction "D1_3") (pintype "bidirectional"))
    )
    (net (code "36") (name "MP_P2") (class "Default")
      (node (ref "J4") (pin "2") (pinfunction "2_2") (pintype "passive"))
      (node (ref "U20") (pin "3") (pinfunction "D1_3") (pintype "bidirectional"))
    )
    (net (code "37") (name "MP_P3") (class "Default")
      (node (ref "J10") (pin "3") (pinfunction "3_3") (pintype "passive"))
      (node (ref "J10") (pin "4") (pinfunction "4_4") (pintype "passive"))
      (node (ref "J10") (pin "5") (pinfunction "5_5") (pintype "passive"))
      (node (ref "J10") (pin "6") (pinfunction "6_6") (pintype "passive"))
      (node (ref "J4") (pin "3") (pinfunction "3_3") (pintype "passive"))
    )
    (net (code "38") (name "MP_P4") (class "Default")
      (node (ref "J4") (pin "4") (pinfunction "4_4") (pintype "passive"))
      (node (ref "U10") (pin "1") (pinfunction "A/C_1") (pintype "passive"))
      (node (ref "U19") (pin "4") (pinfunction "D2_4") (pintype "bidirectional"))
      (node (ref "U9") (pin "4") (pinfunction "D2_4") (pintype "bidirectional"))
    )
    (net (code "39") (name "MP_P5") (class "Default")
      (node (ref "J4") (pin "5") (pinfunction "5_5") (pintype "passive"))
      (node (ref "U18") (pin "1") (pinfunction "A/C_1") (pintype "passive"))
    )
    (net (code "40") (name "MP_P6") (class "Default")
      (node (ref "J4") (pin "6") (pinfunction "6_6") (pintype "passive"))
      (node (ref "U5") (pin "1") (pinfunction "A/C_1") (pintype "passive"))
    )
    (net (code "41") (name "MP_P7") (class "Default")
      (node (ref "J4") (pin "7") (pinfunction "7_7") (pintype "passive"))
      (node (ref "U9") (pin "3") (pinfunction "D1_3") (pintype "bidirectional"))
    )
    (net (code "42") (name "MP_P9") (class "Default")
      (node (ref "J4") (pin "9") (pinfunction "9_9") (pintype "passive"))
      (node (ref "U11") (pin "1") (pinfunction "A/C_1") (pintype "passive"))
      (node (ref "U19") (pin "3") (pinfunction "D1_3") (pintype "bidirectional"))
    )
    (net (code "43") (name "MP_P10") (class "Default")
      (node (ref "J4") (pin "10") (pinfunction "10_10") (pintype "passive"))
      (node (ref "K1") (pin "NO") (pinfunction "1_NO") (pintype "bidirectional"))
      (node (ref "R10") (pin "1") (pinfunction "1_1") (pintype "passive"))
      (node (ref "R20") (pin "1") (pinfunction "1_1") (pintype "passive"))
      (node (ref "R5") (pin "1") (pinfunction "1_1") (pintype "passive"))
      (node (ref "R9") (pin "1") (pinfunction "1_1") (pintype "passive"))
    )
    (net (code "44") (name "MP_P11") (class "Default")
      (node (ref "J4") (pin "11") (pinfunction "11_11") (pintype "passive"))
      (node (ref "K1") (pin "C") (pinfunction "3_C") (pintype "bidirectional"))
    )
    (net (code "45") (name "Net-(A1-PK7)") (class "Default")
      (node (ref "A1") (pin "D69") (pinfunction "PK7_D69") (pintype "bidirectional"))
      (node (ref "R1") (pin "2") (pinfunction "2_2") (pintype "passive"))
    )
    (net (code "46") (name "Net-(D1-ANODE)") (class "Default")
      (node (ref "D1") (pin "1") (pinfunction "ANODE_1") (pintype "bidirectional"))
      (node (ref "U27") (pin "1") (pinfunction "B_1") (pintype "passive"))
    )
    (net (code "47") (name "Net-(D1-CATHODE)") (class "Default")
      (node (ref "C1") (pin "1") (pinfunction "1_1") (pintype "passive"))
      (node (ref "D1") (pin "3") (pinfunction "CATHODE_3") (pintype "bidirectional"))
      (node (ref "R45") (pin "2") (pinfunction "2_2") (pintype "passive"))
    )
    (net (code "48") (name "Net-(D2-ANODE)") (class "Default")
      (node (ref "D2") (pin "1") (pinfunction "ANODE_1") (pintype "bidirectional"))
      (node (ref "U28") (pin "1") (pinfunction "B_1") (pintype "passive"))
    )
    (net (code "49") (name "Net-(D2-CATHODE)") (class "Default")
      (node (ref "C2") (pin "1") (pinfunction "1_1") (pintype "passive"))
      (node (ref "D2") (pin "3") (pinfunction "CATHODE_3") (pintype "bidirectional"))
      (node (ref "R46") (pin "2") (pinfunction "2_2") (pintype "passive"))
    )
    (net (code "50") (name "Net-(K1-4)") (class "Default")
      (node (ref "K1") (pin "L1") (pinfunction "4_L1") (pintype "bidirectional"))
      (node (ref "U25") (pin "3") (pinfunction "D1_3") (pintype "bidirectional"))
    )
    (net (code "51") (name "Net-(R17-Pad2)") (class "Default")
      (node (ref "R17") (pin "2") (pinfunction "2_2") (pintype "passive"))
      (node (ref "R21") (pin "1") (pinfunction "1_1") (pintype "passive"))
    )
    (net (code "52") (name "Net-(R18-Pad2)") (class "Default")
      (node (ref "R18") (pin "2") (pinfunction "2_2") (pintype "passive"))
      (node (ref "R22") (pin "1") (pinfunction "1_1") (pintype "passive"))
    )
    (net (code "53") (name "Net-(R19-Pad2)") (class "Default")
      (node (ref "R19") (pin "2") (pinfunction "2_2") (pintype "passive"))
      (node (ref "R23") (pin "1") (pinfunction "1_1") (pintype "passive"))
    )
    (net (code "54") (name "Net-(R20-Pad2)") (class "Default")
      (node (ref "R20") (pin "2") (pinfunction "2_2") (pintype "passive"))
      (node (ref "R24") (pin "1") (pinfunction "1_1") (pintype "passive"))
    )
    (net (code "55") (name "Net-(R21-Pad2)") (class "Default")
      (node (ref "R21") (pin "2") (pinfunction "2_2") (pintype "passive"))
      (node (ref "R25") (pin "1") (pinfunction "1_1") (pintype "passive"))
    )
    (net (code "56") (name "Net-(R22-Pad2)") (class "Default")
      (node (ref "R22") (pin "2") (pinfunction "2_2") (pintype "passive"))
      (node (ref "R26") (pin "1") (pinfunction "1_1") (pintype "passive"))
    )
    (net (code "57") (name "Net-(R23-Pad2)") (class "Default")
      (node (ref "R23") (pin "2") (pinfunction "2_2") (pintype "passive"))
      (node (ref "R27") (pin "1") (pinfunction "1_1") (pintype "passive"))
    )
    (net (code "58") (name "Net-(R24-Pad2)") (class "Default")
      (node (ref "R24") (pin "2") (pinfunction "2_2") (pintype "passive"))
      (node (ref "R28") (pin "1") (pinfunction "1_1") (pintype "passive"))
    )
    (net (code "59") (name "Net-(R35-Pad2)") (class "Default")
      (node (ref "R35") (pin "2") (pinfunction "2_2") (pintype "passive"))
      (node (ref "R37") (pin "1") (pinfunction "1_1") (pintype "passive"))
    )
    (net (code "60") (name "Net-(R36-Pad2)") (class "Default")
      (node (ref "R36") (pin "2") (pinfunction "2_2") (pintype "passive"))
      (node (ref "R38") (pin "1") (pinfunction "1_1") (pintype "passive"))
    )
    (net (code "61") (name "Net-(R37-Pad2)") (class "Default")
      (node (ref "R37") (pin "2") (pinfunction "2_2") (pintype "passive"))
      (node (ref "R39") (pin "1") (pinfunction "1_1") (pintype "passive"))
    )
    (net (code "62") (name "Net-(R38-Pad2)") (class "Default")
      (node (ref "R38") (pin "2") (pinfunction "2_2") (pintype "passive"))
      (node (ref "R40") (pin "1") (pinfunction "1_1") (pintype "passive"))
    )
    (net (code "63") (name "Net-(R47-Pad1)") (class "Default")
      (node (ref "R47") (pin "1") (pinfunction "1_1") (pintype "passive"))
      (node (ref "U27") (pin "2") (pinfunction "C_2") (pintype "passive"))
      (node (ref "U27") (pin "4") (pinfunction "C_4") (pintype "passive"))
    )
    (net (code "64") (name "Net-(R48-Pad1)") (class "Default")
      (node (ref "R48") (pin "1") (pinfunction "1_1") (pintype "passive"))
      (node (ref "U28") (pin "2") (pinfunction "C_2") (pintype "passive"))
      (node (ref "U28") (pin "4") (pinfunction "C_4") (pintype "passive"))
    )
    (net (code "65") (name "Net-(U3-C{slash}A)") (class "Default")
      (node (ref "R3") (pin "2") (pinfunction "2_2") (pintype "passive"))
      (node (ref "U3") (pin "2") (pinfunction "C/A_2") (pintype "passive"))
    )
    (net (code "66") (name "Net-(U4-C{slash}A)") (class "Default")
      (node (ref "R4") (pin "2") (pinfunction "2_2") (pintype "passive"))
      (node (ref "U4") (pin "2") (pinfunction "C/A_2") (pintype "passive"))
    )
    (net (code "67") (name "Net-(U5-C{slash}A)") (class "Default")
      (node (ref "R5") (pin "2") (pinfunction "2_2") (pintype "passive"))
      (node (ref "U5") (pin "2") (pinfunction "C/A_2") (pintype "passive"))
    )
    (net (code "68") (name "Net-(U6-E)") (class "Default")
      (node (ref "U6") (pin "3") (pinfunction "E_3") (pintype "passive"))
      (node (ref "U8") (pin "1") (pinfunction "A_1") (pintype "bidirectional"))
    )
    (net (code "69") (name "Net-(U7-E)") (class "Default")
      (node (ref "U7") (pin "3") (pinfunction "E_3") (pintype "passive"))
      (node (ref "U9") (pin "1") (pinfunction "A_1") (pintype "bidirectional"))
    )
    (net (code "70") (name "Net-(U8-K)") (class "Default")
      (node (ref "R12") (pin "2") (pinfunction "2_2") (pintype "passive"))
      (node (ref "U8") (pin "2") (pinfunction "K_2") (pintype "bidirectional"))
    )
    (net (code "71") (name "Net-(U9-K)") (class "Default")
      (node (ref "R13") (pin "2") (pinfunction "2_2") (pintype "passive"))
      (node (ref "U9") (pin "2") (pinfunction "K_2") (pintype "bidirectional"))
    )
    (net (code "72") (name "Net-(U10-C{slash}A)") (class "Default")
      (node (ref "R9") (pin "2") (pinfunction "2_2") (pintype "passive"))
      (node (ref "U10") (pin "2") (pinfunction "C/A_2") (pintype "passive"))
    )
    (net (code "73") (name "Net-(U11-C{slash}A)") (class "Default")
      (node (ref "R10") (pin "2") (pinfunction "2_2") (pintype "passive"))
      (node (ref "U11") (pin "2") (pinfunction "C/A_2") (pintype "passive"))
    )
    (net (code "74") (name "Net-(U12-C{slash}A)") (class "Default")
      (node (ref "R11") (pin "2") (pinfunction "2_2") (pintype "passive"))
      (node (ref "U12") (pin "2") (pinfunction "C/A_2") (pintype "passive"))
    )
    (net (code "75") (name "Net-(U13-E)") (class "Default")
      (node (ref "U13") (pin "3") (pinfunction "E_3") (pintype "passive"))
      (node (ref "U19") (pin "1") (pinfunction "A_1") (pintype "bidirectional"))
    )
    (net (code "76") (name "Net-(U14-E)") (class "Default")
      (node (ref "U14") (pin "3") (pinfunction "E_3") (pintype "passive"))
      (node (ref "U20") (pin "1") (pinfunction "A_1") (pintype "bidirectional"))
    )
    (net (code "77") (name "Net-(U15-C{slash}A)") (class "Default")
      (node (ref "R25") (pin "2") (pinfunction "2_2") (pintype "passive"))
      (node (ref "U15") (pin "2") (pinfunction "C/A_2") (pintype "passive"))
    )
    (net (code "78") (name "Net-(U16-C{slash}A)") (class "Default")
      (node (ref "R26") (pin "2") (pinfunction "2_2") (pintype "passive"))
      (node (ref "U16") (pin "2") (pinfunction "C/A_2") (pintype "passive"))
    )
    (net (code "79") (name "Net-(U17-C{slash}A)") (class "Default")
      (node (ref "R27") (pin "2") (pinfunction "2_2") (pintype "passive"))
      (node (ref "U17") (pin "2") (pinfunction "C/A_2") (pintype "passive"))
    )
    (net (code "80") (name "Net-(U18-C{slash}A)") (class "Default")
      (node (ref "R28") (pin "2") (pinfunction "2_2") (pintype "passive"))
      (node (ref "U18") (pin "2") (pinfunction "C/A_2") (pintype "passive"))
    )
    (net (code "81") (name "Net-(U19-K)") (class "Default")
      (node (ref "R29") (pin "2") (pinfunction "2_2") (pintype "passive"))
      (node (ref "U19") (pin "2") (pinfunction "K_2") (pintype "bidirectional"))
    )
    (net (code "82") (name "Net-(U20-K)") (class "Default")
      (node (ref "R30") (pin "2") (pinfunction "2_2") (pintype "passive"))
      (node (ref "U20") (pin "2") (pinfunction "K_2") (pintype "bidirectional"))
    )
    (net (code "83") (name "Net-(U21-E)") (class "Default")
      (node (ref "U21") (pin "3") (pinfunction "E_3") (pintype "passive"))
      (node (ref "U25") (pin "1") (pinfunction "A_1") (pintype "bidirectional"))
    )
    (net (code "84") (name "Net-(U22-E)") (class "Default")
      (node (ref "U22") (pin "3") (pinfunction "E_3") (pintype "passive"))
      (node (ref "U26") (pin "1") (pinfunction "A_1") (pintype "bidirectional"))
    )
    (net (code "85") (name "Net-(U23-C{slash}A)") (class "Default")
      (node (ref "R39") (pin "2") (pinfunction "2_2") (pintype "passive"))
      (node (ref "U23") (pin "2") (pinfunction "C/A_2") (pintype "passive"))
    )
    (net (code "86") (name "Net-(U24-C{slash}A)") (class "Default")
      (node (ref "R40") (pin "2") (pinfunction "2_2") (pintype "passive"))
      (node (ref "U24") (pin "2") (pinfunction "C/A_2") (pintype "passive"))
    )
    (net (code "87") (name "Net-(U25-K)") (class "Default")
      (node (ref "R43") (pin "1") (pinfunction "1_1") (pintype "passive"))
      (node (ref "U25") (pin "2") (pinfunction "K_2") (pintype "bidirectional"))
    )
    (net (code "88") (name "Net-(U26-K)") (class "Default")
      (node (ref "R42") (pin "2") (pinfunction "2_2") (pintype "passive"))
      (node (ref "U26") (pin "2") (pinfunction "K_2") (pintype "bidirectional"))
    )
    (net (code "89") (name "Net-(U27-E)") (class "Default")
      (node (ref "U27") (pin "3") (pinfunction "E_3") (pintype "passive"))
      (node (ref "U30") (pin "1") (pinfunction "A/C_1") (pintype "passive"))
    )
    (net (code "90") (name "Net-(U28-E)") (class "Default")
      (node (ref "U28") (pin "3") (pinfunction "E_3") (pintype "passive"))
      (node (ref "U29") (pin "1") (pinfunction "A/C_1") (pintype "passive"))
    )
    (net (code "91") (name "PM_P1") (class "Default")
      (node (ref "J3") (pin "1") (pinfunction "1_1") (pintype "passive"))
      (node (ref "U17") (pin "1") (pinfunction "A/C_1") (pintype "passive"))
    )
    (net (code "92") (name "PM_P2") (class "Default")
      (node (ref "J3") (pin "2") (pinfunction "2_2") (pintype "passive"))
      (node (ref "R19") (pin "1") (pinfunction "1_1") (pintype "passive"))
    )
    (net (code "93") (name "PM_PWR_SIGNAL") (class "Default")
      (node (ref "A1") (pin "D60") (pinfunction "PF6_D60") (pintype "bidirectional"))
      (node (ref "R33") (pin "1") (pinfunction "1_1") (pintype "passive"))
      (node (ref "U17") (pin "4") (pinfunction "CO_4") (pintype "passive"))
    )
    (net (code "94") (name "PON_SIGNAL") (class "Default")
      (node (ref "A1") (pin "D61") (pinfunction "PF7_D61") (pintype "bidirectional"))
      (node (ref "R14") (pin "1") (pinfunction "1_1") (pintype "passive"))
      (node (ref "U10") (pin "4") (pinfunction "CO_4") (pintype "passive"))
    )
    (net (code "95") (name "POWER_CTRL") (class "Default")
      (node (ref "A1") (pin "D12") (pinfunction "PB6_D12") (pintype "bidirectional"))
      (node (ref "U21") (pin "1") (pinfunction "B_1") (pintype "passive"))
    )
    (net (code "96") (name "PUMP_CTRL") (class "Default")
      (node (ref "A1") (pin "D11") (pinfunction "PB5_D11") (pintype "bidirectional"))
      (node (ref "U7") (pin "1") (pinfunction "B_1") (pintype "passive"))
    )
    (net (code "97") (name "PWM_HIGH_SIGNAL") (class "Default")
      (node (ref "A1") (pin "D4") (pinfunction "PG5_D4") (pintype "bidirectional"))
      (node (ref "R50") (pin "1") (pinfunction "1_1") (pintype "passive"))
      (node (ref "U30") (pin "4") (pinfunction "CO_4") (pintype "passive"))
    )
    (net (code "98") (name "PWM_LOW_SIGNAL") (class "Default")
      (node (ref "A1") (pin "D5") (pinfunction "PE3_D5") (pintype "bidirectional"))
      (node (ref "R49") (pin "1") (pinfunction "1_1") (pintype "passive"))
      (node (ref "U29") (pin "4") (pinfunction "CO_4") (pintype "passive"))
    )
    (net (code "99") (name "RST") (class "Default")
      (node (ref "A1") (pin "D22") (pinfunction "D22_D22") (pintype "bidirectional"))
      (node (ref "A2") (pin "7") (pinfunction "RST_7") (pintype "bidirectional"))
    )
    (net (code "100") (name "R_BSKT_SIGNAL") (class "Default")
      (node (ref "A1") (pin "D55") (pinfunction "PF1_D55") (pintype "bidirectional"))
      (node (ref "R7") (pin "1") (pinfunction "1_1") (pintype "passive"))
      (node (ref "U4") (pin "4") (pinfunction "CO_4") (pintype "passive"))
    )
    (net (code "101") (name "SCK") (class "Default")
      (node (ref "A1") (pin "D52") (pinfunction "D52_D52") (pintype "bidirectional"))
      (node (ref "A2") (pin "11") (pinfunction "SCK_11") (pintype "bidirectional"))
    )
    (net (code "102") (name "SP_A1") (class "Default")
      (node (ref "A1") (pin "D54") (pinfunction "PF0_D54") (pintype "bidirectional"))
      (node (ref "J11") (pin "2") (pinfunction "2_2") (pintype "passive"))
      (node (ref "J9") (pin "1") (pinfunction "1_1") (pintype "passive"))
    )
    (net (code "103") (name "SP_D1") (class "Default")
      (node (ref "A1") (pin "D7") (pinfunction "PH4_D7") (pintype "bidirectional"))
      (node (ref "J9") (pin "6") (pinfunction "6_6") (pintype "passive"))
    )
    (net (code "104") (name "SP_D2") (class "Default")
      (node (ref "A1") (pin "D6") (pinfunction "PH3_D6") (pintype "bidirectional"))
      (node (ref "J9") (pin "5") (pinfunction "5_5") (pintype "passive"))
    )
    (net (code "105") (name "SVR_P1") (class "Default")
      (node (ref "J1") (pin "1") (pinfunction "1_1") (pintype "passive"))
      (node (ref "U26") (pin "3") (pinfunction "D1_3") (pintype "bidirectional"))
    )
    (net (code "106") (name "SVR_P3") (class "Default")
      (node (ref "J1") (pin "3") (pinfunction "3_3") (pintype "passive"))
      (node (ref "U26") (pin "4") (pinfunction "D2_4") (pintype "bidirectional"))
    )
    (net (code "107") (name "SV_P1") (class "Default")
      (node (ref "J6") (pin "1") (pinfunction "1_1") (pintype "passive"))
      (node (ref "R18") (pin "1") (pinfunction "1_1") (pintype "passive"))
    )
    (net (code "108") (name "SV_P4") (class "Default")
      (node (ref "J6") (pin "4") (pinfunction "4_4") (pintype "passive"))
      (node (ref "U16") (pin "1") (pinfunction "A/C_1") (pintype "passive"))
    )
    (net (code "109") (name "S_VALVE_CTRL") (class "Default")
      (node (ref "A1") (pin "D9") (pinfunction "PH6_D9") (pintype "bidirectional"))
      (node (ref "U22") (pin "1") (pinfunction "B_1") (pintype "passive"))
    )
    (net (code "110") (name "S_VALVE_SIGNAL") (class "Default")
      (node (ref "A1") (pin "D59") (pinfunction "PF5_D59") (pintype "bidirectional"))
      (node (ref "R32") (pin "1") (pinfunction "1_1") (pintype "passive"))
      (node (ref "U16") (pin "4") (pinfunction "CO_4") (pintype "passive"))
    )
    (net (code "111") (name "TH_CALL_CTRL") (class "Default")
      (node (ref "A1") (pin "D10") (pinfunction "PB4_D10") (pintype "bidirectional"))
      (node (ref "U13") (pin "1") (pinfunction "B_1") (pintype "passive"))
    )
    (net (code "112") (name "TH_CALL_SIGNAL") (class "Default")
      (node (ref "R15") (pin "1") (pinfunction "1_1") (pintype "passive"))
      (node (ref "U11") (pin "4") (pinfunction "CO_4") (pintype "passive"))
    )
    (net (code "113") (name "unconnected-(A1-+5V_2-Pad+5V-2)") (class "Default")
      (node (ref "A1") (pin "+5V-2") (pinfunction "+5V_2_+5V-2") (pintype "bidirectional"))
    )
    (net (code "114") (name "unconnected-(A1-+5V_3-Pad+5V-3)") (class "Default")
      (node (ref "A1") (pin "+5V-3") (pinfunction "+5V_3_+5V-3") (pintype "bidirectional"))
    )
    (net (code "115") (name "unconnected-(A1-GND4-PadGND-4)") (class "Default")
      (node (ref "A1") (pin "GND-4") (pinfunction "GND4_GND-4") (pintype "bidirectional"))
    )
    (net (code "116") (name "unconnected-(A1-GND5-PadGND-5)") (class "Default")
      (node (ref "A1") (pin "GND-5") (pinfunction "GND5_GND-5") (pintype "bidirectional"))
    )
    (net (code "117") (name "unconnected-(A1-PD0-2-PadD21-2)") (class "Default")
      (node (ref "A1") (pin "D21-2") (pinfunction "PD0-2_D21-2") (pintype "bidirectional"))
    )
    (net (code "118") (name "unconnected-(A1-PD0-PadD21)") (class "Default")
      (node (ref "A1") (pin "D21") (pinfunction "PD0_D21") (pintype "bidirectional"))
    )
    (net (code "119") (name "unconnected-(A1-PD1-2-PadD20-2)") (class "Default")
      (node (ref "A1") (pin "D20-2") (pinfunction "PD1-2_D20-2") (pintype "bidirectional"))
    )
    (net (code "120") (name "unconnected-(A1-PD1-PadD20)") (class "Default")
      (node (ref "A1") (pin "D20") (pinfunction "PD1_D20") (pintype "bidirectional"))
    )
    (net (code "121") (name "unconnected-(A1-PD2-PadD19)") (class "Default")
      (node (ref "A1") (pin "D19") (pinfunction "PD2_D19") (pintype "bidirectional"))
    )
    (net (code "122") (name "unconnected-(A1-PD3-PadD18)") (class "Default")
      (node (ref "A1") (pin "D18") (pinfunction "PD3_D18") (pintype "bidirectional"))
    )
    (net (code "123") (name "unconnected-(A1-PE0-PadD0)") (class "Default")
      (node (ref "A1") (pin "D0") (pinfunction "PE0_D0") (pintype "bidirectional"))
    )
    (net (code "124") (name "unconnected-(A1-PE1-PadD1)") (class "Default")
      (node (ref "A1") (pin "D1") (pinfunction "PE1_D1") (pintype "bidirectional"))
    )
    (net (code "125") (name "unconnected-(A1-PE4-PadD2)") (class "Default")
      (node (ref "A1") (pin "D2") (pinfunction "PE4_D2") (pintype "bidirectional"))
    )
    (net (code "126") (name "unconnected-(A1-PE5-PadD3)") (class "Default")
      (node (ref "A1") (pin "D3") (pinfunction "PE5_D3") (pintype "bidirectional"))
    )
    (net (code "127") (name "unconnected-(A1-PH0-PadD17)") (class "Default")
      (node (ref "A1") (pin "D17") (pinfunction "PH0_D17") (pintype "bidirectional"))
    )
    (net (code "128") (name "unconnected-(A1-PH1-PadD16)") (class "Default")
      (node (ref "A1") (pin "D16") (pinfunction "PH1_D16") (pintype "bidirectional"))
    )
    (net (code "129") (name "unconnected-(A1-PH5-PadD8)") (class "Default")
      (node (ref "A1") (pin "D8") (pinfunction "PH5_D8") (pintype "bidirectional"))
    )
    (net (code "130") (name "unconnected-(A1-PJ0-PadD15)") (class "Default")
      (node (ref "A1") (pin "D15") (pinfunction "PJ0_D15") (pintype "bidirectional"))
    )
    (net (code "131") (name "unconnected-(A1-PJ1-PadD14)") (class "Default")
      (node (ref "A1") (pin "D14") (pinfunction "PJ1_D14") (pintype "bidirectional"))
    )
    (net (code "132") (name "unconnected-(A1-Pad+3V3)") (class "Default")
      (node (ref "A1") (pin "+3V3") (pinfunction "+3V3_+3V3") (pintype "bidirectional"))
    )
    (net (code "133") (name "unconnected-(A1-Pad+5V)") (class "Default")
      (node (ref "A1") (pin "+5V") (pinfunction "+5V_+5V") (pintype "bidirectional"))
    )
    (net (code "134") (name "unconnected-(A1-PadAREF)") (class "Default")
      (node (ref "A1") (pin "AREF") (pinfunction "AREF_AREF") (pintype "bidirectional"))
    )
    (net (code "135") (name "unconnected-(A1-PadD24)") (class "Default")
      (node (ref "A1") (pin "D24") (pinfunction "D24_D24") (pintype "bidirectional"))
    )
    (net (code "136") (name "unconnected-(A1-PadD25)") (class "Default")
      (node (ref "A1") (pin "D25") (pinfunction "D25_D25") (pintype "bidirectional"))
    )
    (net (code "137") (name "unconnected-(A1-PadD26)") (class "Default")
      (node (ref "A1") (pin "D26") (pinfunction "D26_D26") (pintype "bidirectional"))
    )
    (net (code "138") (name "unconnected-(A1-PadD27)") (class "Default")
      (node (ref "A1") (pin "D27") (pinfunction "D27_D27") (pintype "bidirectional"))
    )
    (net (code "139") (name "unconnected-(A1-PadD28)") (class "Default")
      (node (ref "A1") (pin "D28") (pinfunction "D28_D28") (pintype "bidirectional"))
    )
    (net (code "140") (name "unconnected-(A1-PadD29)") (class "Default")
      (node (ref "A1") (pin "D29") (pinfunction "D29_D29") (pintype "bidirectional"))
    )
    (net (code "141") (name "unconnected-(A1-PadD30)") (class "Default")
      (node (ref "A1") (pin "D30") (pinfunction "D30_D30") (pintype "bidirectional"))
    )
    (net (code "142") (name "unconnected-(A1-PadD31)") (class "Default")
      (node (ref "A1") (pin "D31") (pinfunction "D31_D31") (pintype "bidirectional"))
    )
    (net (code "143") (name "unconnected-(A1-PadD32)") (class "Default")
      (node (ref "A1") (pin "D32") (pinfunction "D32_D32") (pintype "bidirectional"))
    )
    (net (code "144") (name "unconnected-(A1-PadD33)") (class "Default")
      (node (ref "A1") (pin "D33") (pinfunction "D33_D33") (pintype "bidirectional"))
    )
    (net (code "145") (name "unconnected-(A1-PadD34)") (class "Default")
      (node (ref "A1") (pin "D34") (pinfunction "D34_D34") (pintype "bidirectional"))
    )
    (net (code "146") (name "unconnected-(A1-PadD35)") (class "Default")
      (node (ref "A1") (pin "D35") (pinfunction "D35_D35") (pintype "bidirectional"))
    )
    (net (code "147") (name "unconnected-(A1-PadD36)") (class "Default")
      (node (ref "A1") (pin "D36") (pinfunction "D36_D36") (pintype "bidirectional"))
    )
    (net (code "148") (name "unconnected-(A1-PadD37)") (class "Default")
      (node (ref "A1") (pin "D37") (pinfunction "D37_D37") (pintype "bidirectional"))
    )
    (net (code "149") (name "unconnected-(A1-PadD38)") (class "Default")
      (node (ref "A1") (pin "D38") (pinfunction "D38_D38") (pintype "bidirectional"))
    )
    (net (code "150") (name "unconnected-(A1-PadD39)") (class "Default")
      (node (ref "A1") (pin "D39") (pinfunction "D39_D39") (pintype "bidirectional"))
    )
    (net (code "151") (name "unconnected-(A1-PadD40)") (class "Default")
      (node (ref "A1") (pin "D40") (pinfunction "D40_D40") (pintype "bidirectional"))
    )
    (net (code "152") (name "unconnected-(A1-PadD41)") (class "Default")
      (node (ref "A1") (pin "D41") (pinfunction "D41_D41") (pintype "bidirectional"))
    )
    (net (code "153") (name "unconnected-(A1-PadD42)") (class "Default")
      (node (ref "A1") (pin "D42") (pinfunction "D42_D42") (pintype "bidirectional"))
    )
    (net (code "154") (name "unconnected-(A1-PadD43)") (class "Default")
      (node (ref "A1") (pin "D43") (pinfunction "D43_D43") (pintype "bidirectional"))
    )
    (net (code "155") (name "unconnected-(A1-PadD44)") (class "Default")
      (node (ref "A1") (pin "D44") (pinfunction "D44_D44") (pintype "bidirectional"))
    )
    (net (code "156") (name "unconnected-(A1-PadD45)") (class "Default")
      (node (ref "A1") (pin "D45") (pinfunction "D45_D45") (pintype "bidirectional"))
    )
    (net (code "157") (name "unconnected-(A1-PadD46)") (class "Default")
      (node (ref "A1") (pin "D46") (pinfunction "D46_D46") (pintype "bidirectional"))
    )
    (net (code "158") (name "unconnected-(A1-PadD47)") (class "Default")
      (node (ref "A1") (pin "D47") (pinfunction "D47_D47") (pintype "bidirectional"))
    )
    (net (code "159") (name "unconnected-(A1-PadD48)") (class "Default")
      (node (ref "A1") (pin "D48") (pinfunction "D48_D48") (pintype "bidirectional"))
    )
    (net (code "160") (name "unconnected-(A1-PadD49)") (class "Default")
      (node (ref "A1") (pin "D49") (pinfunction "D49_D49") (pintype "bidirectional"))
    )
    (net (code "161") (name "unconnected-(A1-PadIOREF)") (class "Default")
      (node (ref "A1") (pin "IOREF") (pinfunction "IOREF_IOREF") (pintype "bidirectional"))
    )
    (net (code "162") (name "unconnected-(A1-PadNC)") (class "Default")
      (node (ref "A1") (pin "NC") (pinfunction "NC_NC") (pintype "bidirectional"))
    )
    (net (code "163") (name "unconnected-(A1-~{RESET}-Pad!RESET!)") (class "Default")
      (node (ref "A1") (pin "!RESET!") (pinfunction "~{RESET}_!RESET!") (pintype "bidirectional"))
    )
    (net (code "164") (name "unconnected-(A2-+3V3-Pad13)") (class "Default")
      (node (ref "A2") (pin "13") (pinfunction "+3V3_13") (pintype "bidirectional"))
    )
    (net (code "165") (name "unconnected-(A2-LITE-Pad12)") (class "Default")
      (node (ref "A2") (pin "12") (pinfunction "LITE_12") (pintype "bidirectional"))
    )
    (net (code "166") (name "unconnected-(A2-WAIT-Pad6)") (class "Default")
      (node (ref "A2") (pin "6") (pinfunction "WAIT_6") (pintype "bidirectional"))
    )
    (net (code "167") (name "unconnected-(A2-X+-Pad1)") (class "Default")
      (node (ref "A2") (pin "1") (pinfunction "X+_1") (pintype "bidirectional"))
    )
    (net (code "168") (name "unconnected-(A2-X--Pad2)") (class "Default")
      (node (ref "A2") (pin "2") (pinfunction "X-_2") (pintype "bidirectional"))
    )
    (net (code "169") (name "unconnected-(A2-Y+-Pad4)") (class "Default")
      (node (ref "A2") (pin "4") (pinfunction "Y+_4") (pintype "bidirectional"))
    )
    (net (code "170") (name "unconnected-(A2-Y--Pad3)") (class "Default")
      (node (ref "A2") (pin "3") (pinfunction "Y-_3") (pintype "bidirectional"))
    )
    (net (code "171") (name "unconnected-(D1-NOT_CONNECTED-Pad2)") (class "Default")
      (node (ref "D1") (pin "2") (pinfunction "NOT_CONNECTED_2") (pintype "bidirectional"))
    )
    (net (code "172") (name "unconnected-(D2-NOT_CONNECTED-Pad2)") (class "Default")
      (node (ref "D2") (pin "2") (pinfunction "NOT_CONNECTED_2") (pintype "bidirectional"))
    )
    (net (code "173") (name "unconnected-(J1-Pad2)") (class "Default")
      (node (ref "J1") (pin "2") (pinfunction "2_2") (pintype "passive"))
    )
    (net (code "174") (name "unconnected-(J2-Pad8)") (class "Default")
      (node (ref "J2") (pin "8") (pinfunction "8_8") (pintype "passive"))
    )
    (net (code "175") (name "unconnected-(J6-Pad2)") (class "Default")
      (node (ref "J6") (pin "2") (pinfunction "2_2") (pintype "passive"))
    )
    (net (code "176") (name "unconnected-(J6-Pad3)") (class "Default")
      (node (ref "J6") (pin "3") (pinfunction "3_3") (pintype "passive"))
    )
    (net (code "177") (name "unconnected-(K1-2-PadNC)") (class "Default")
      (node (ref "K1") (pin "NC") (pinfunction "2_NC") (pintype "bidirectional"))
    )
  )
)
